# os_-_POC.net
KiCad netlist of a schematic drawn in EAGLE
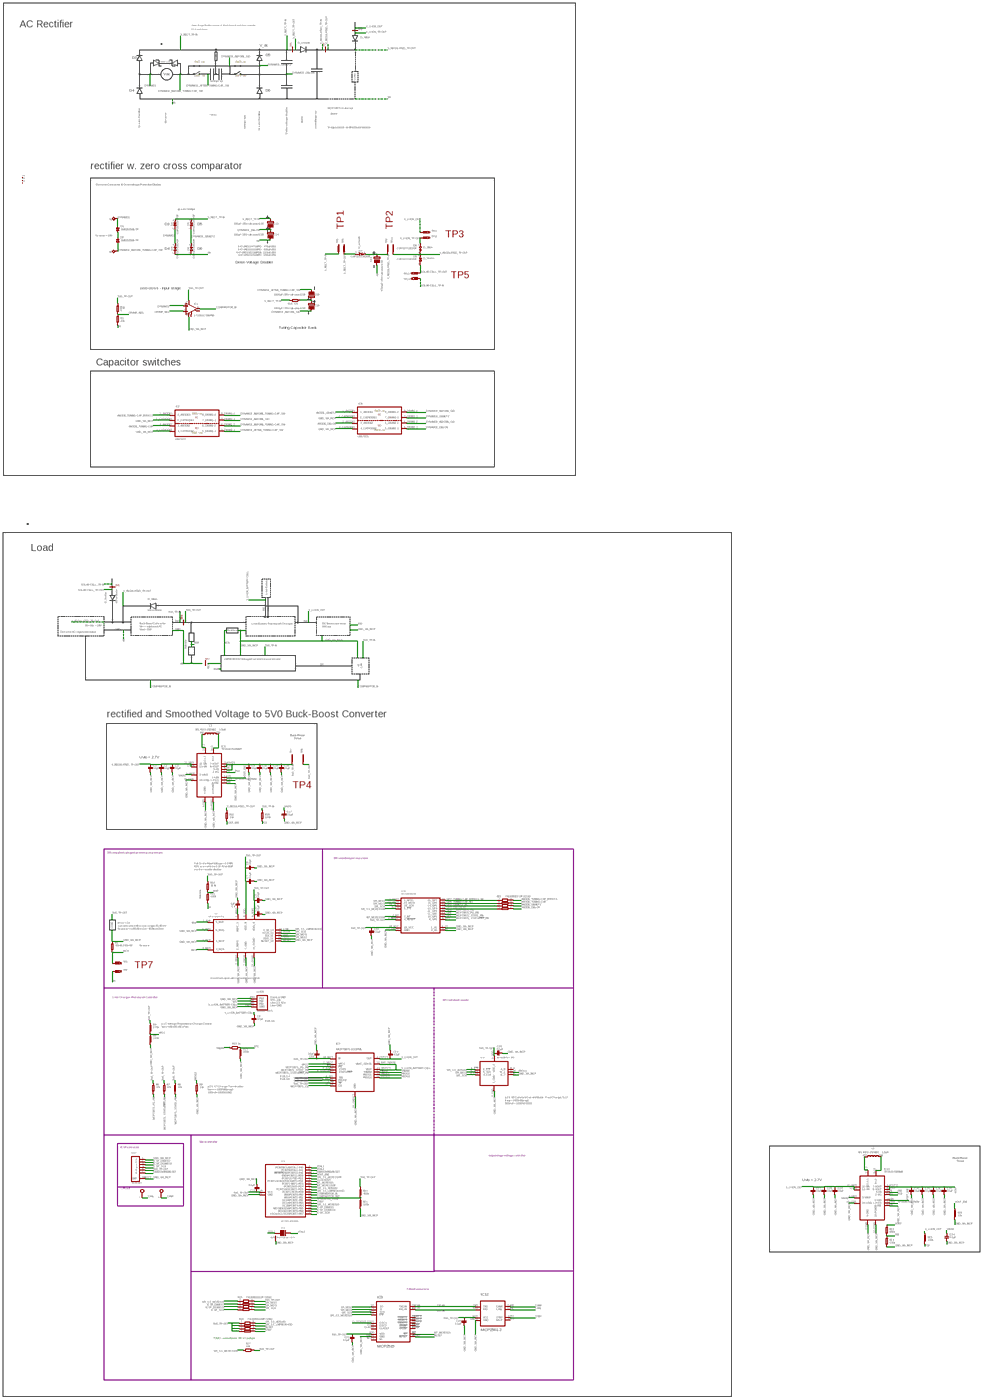
[diagram p0: schematic, sheet 1, overview]
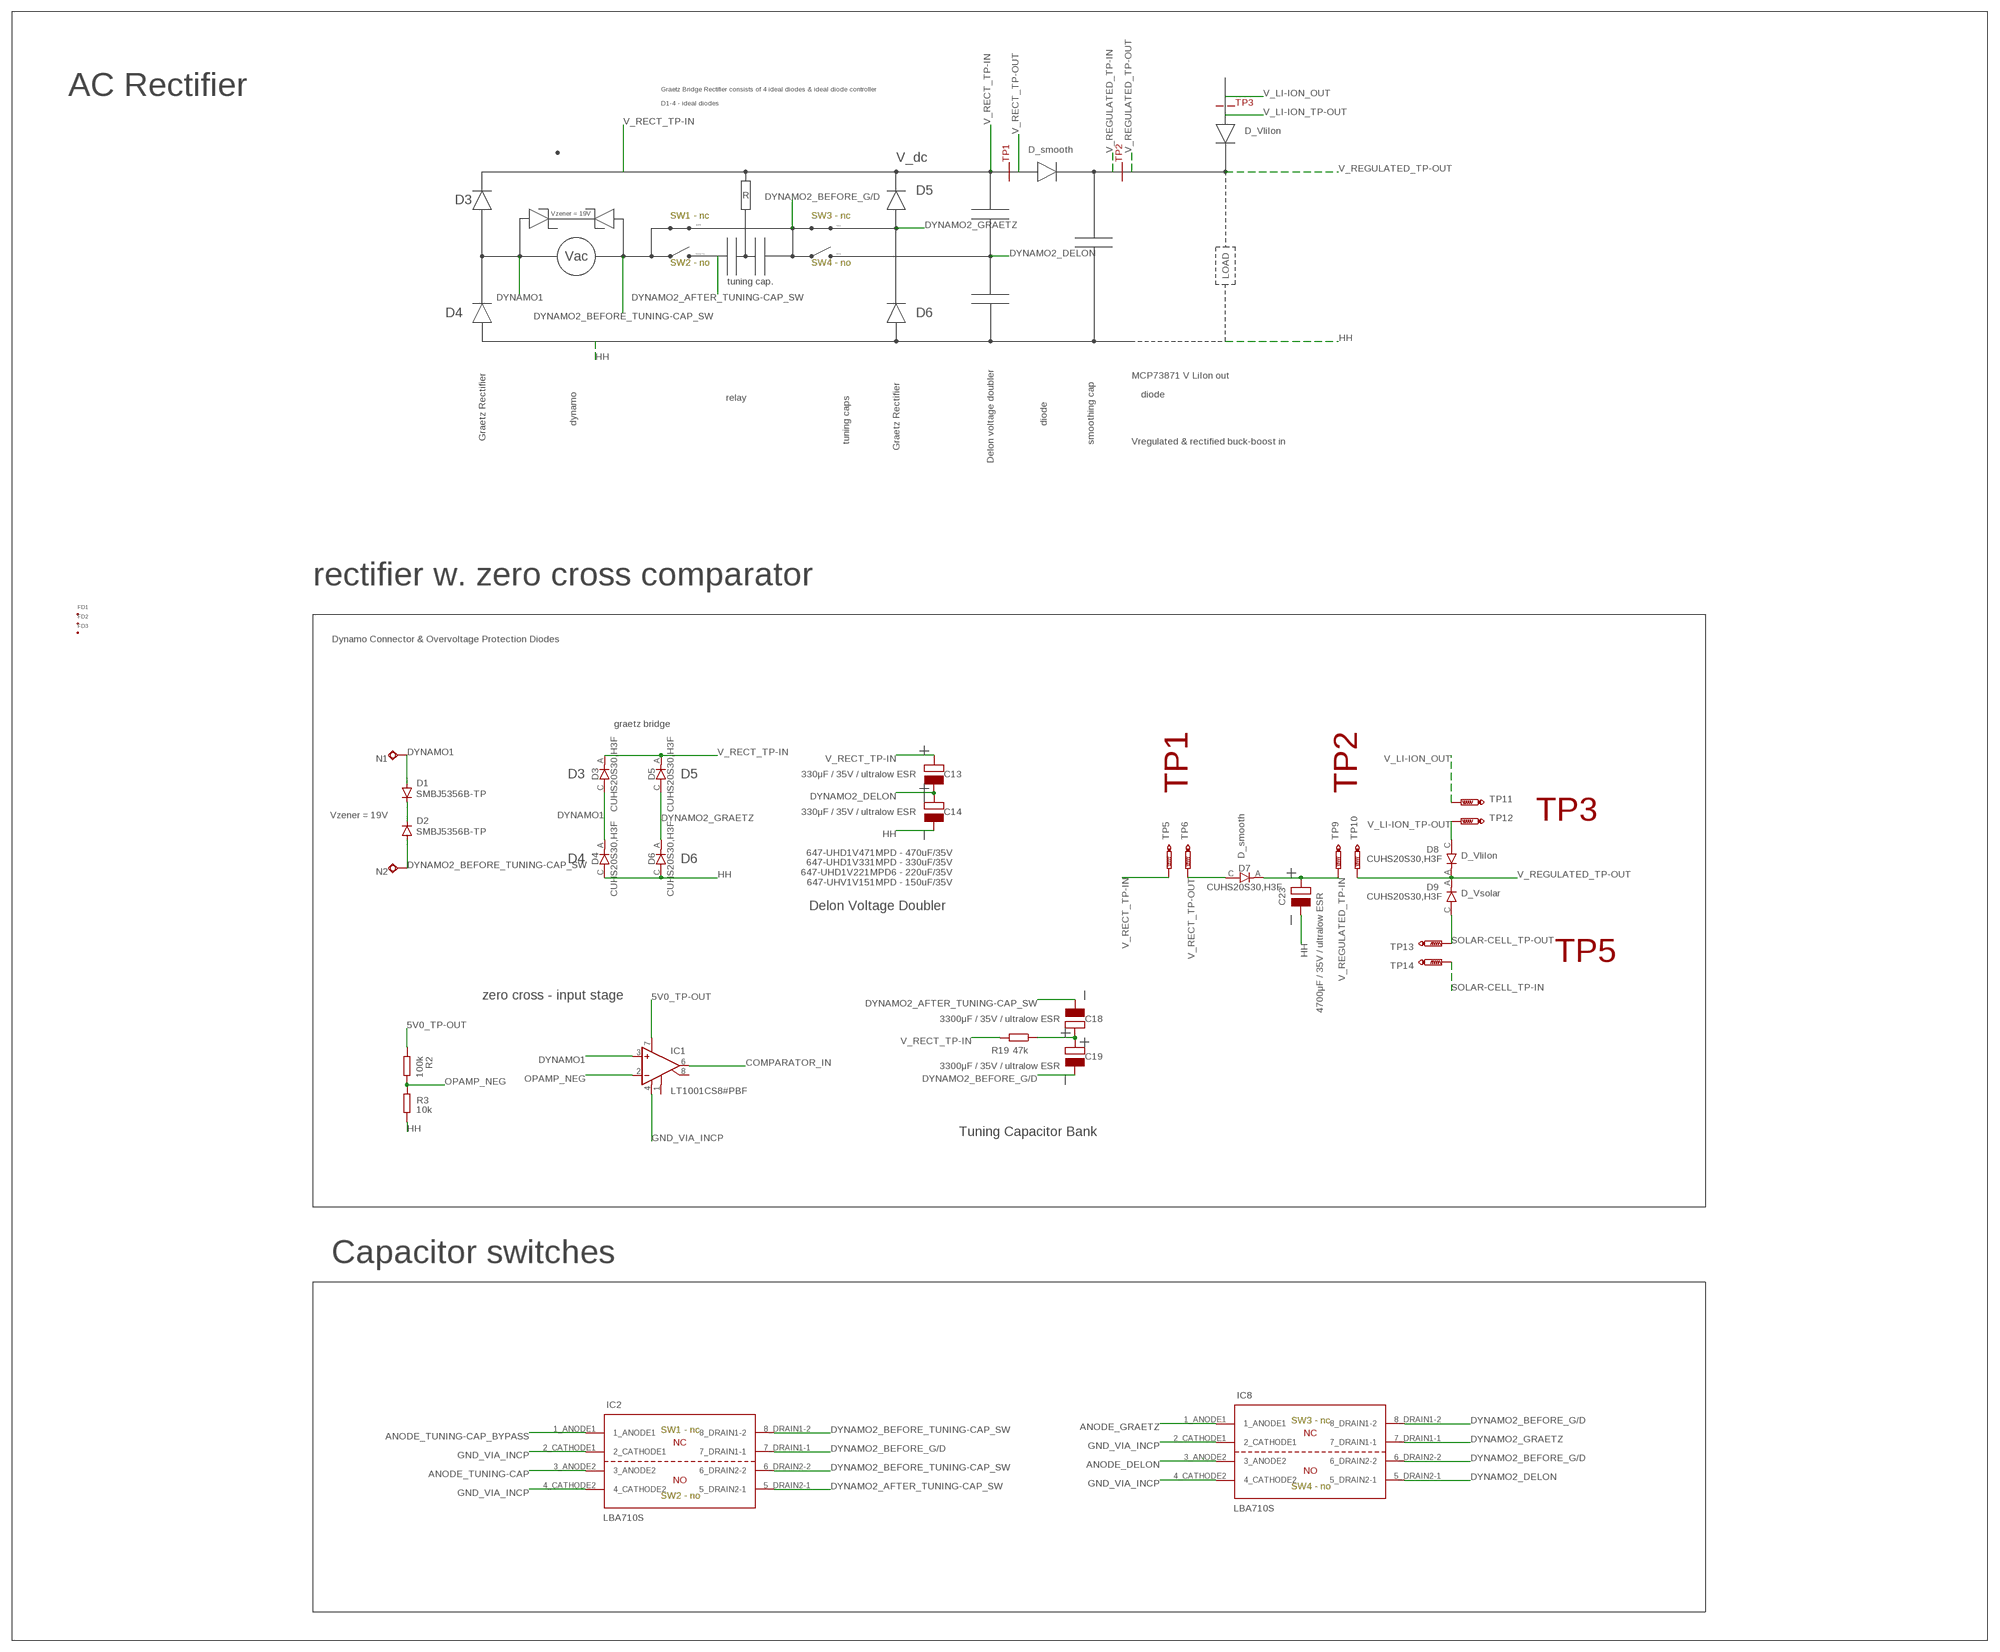
[diagram p1: schematic, sheet 1, part 1 of 5]
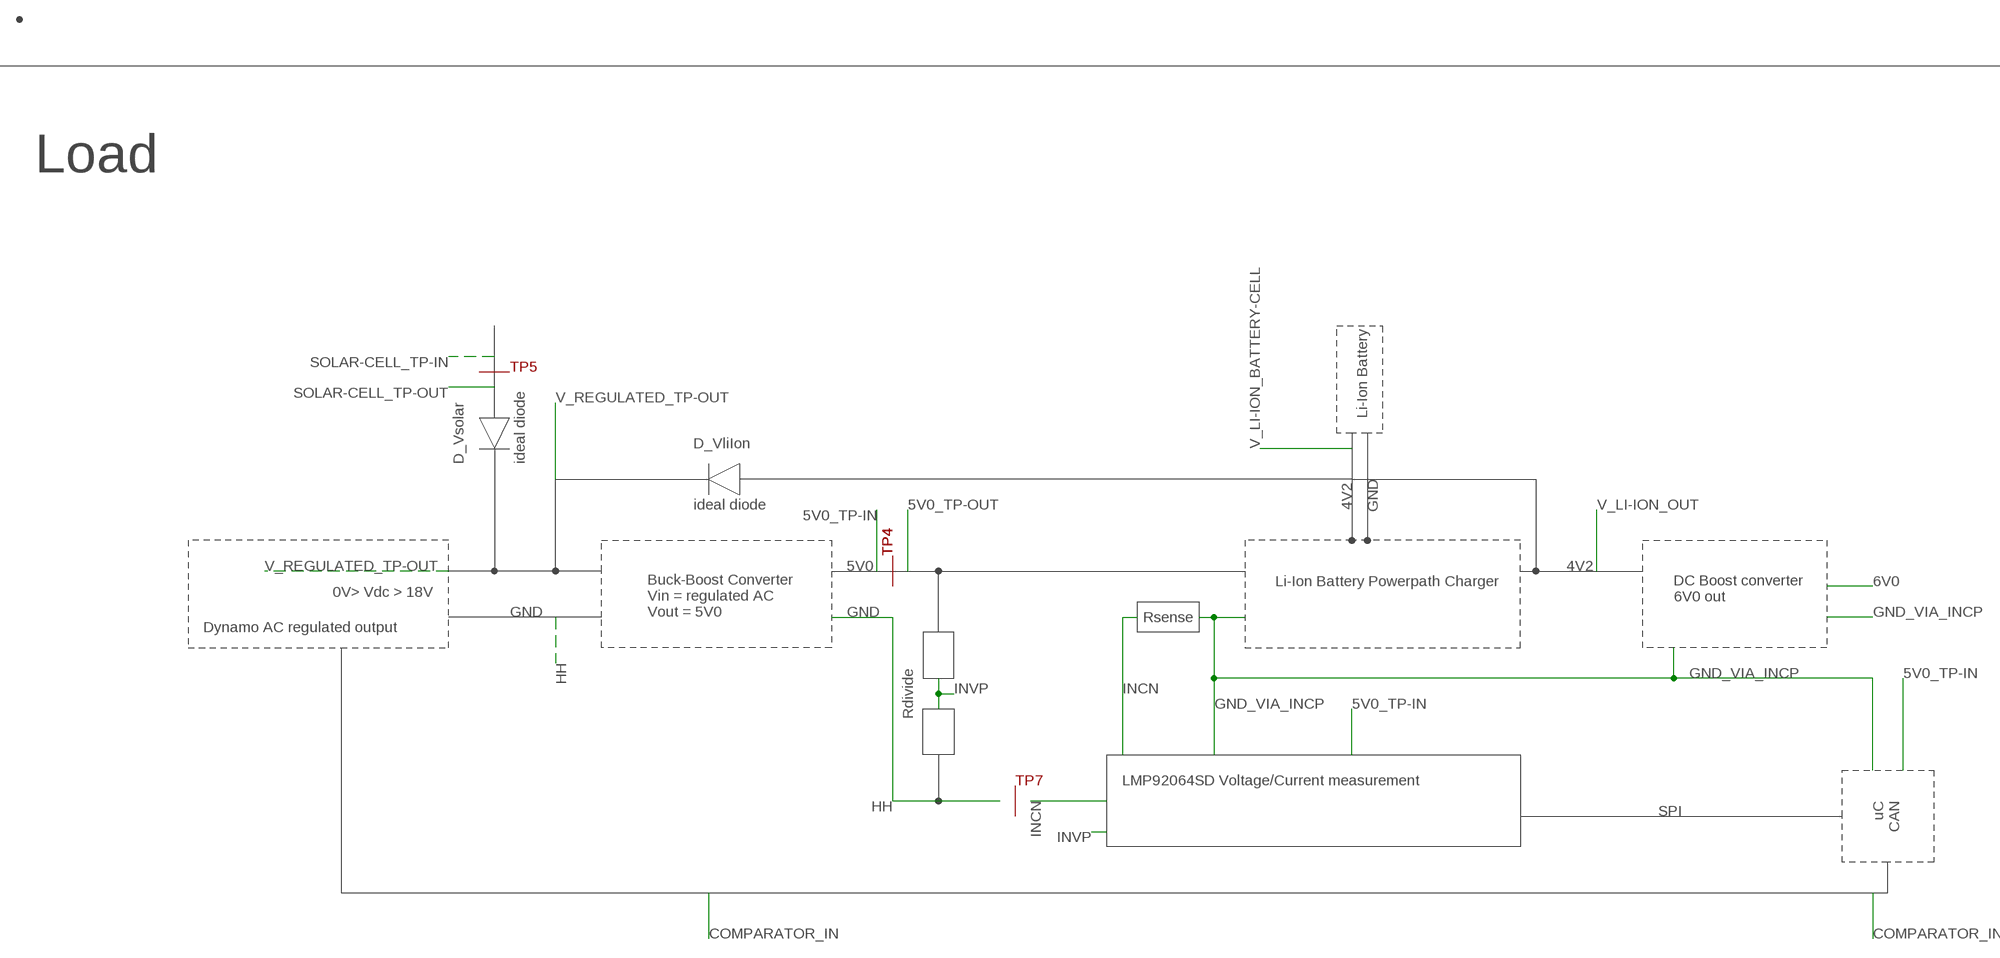
[diagram p2: schematic, sheet 1, part 2 of 5]
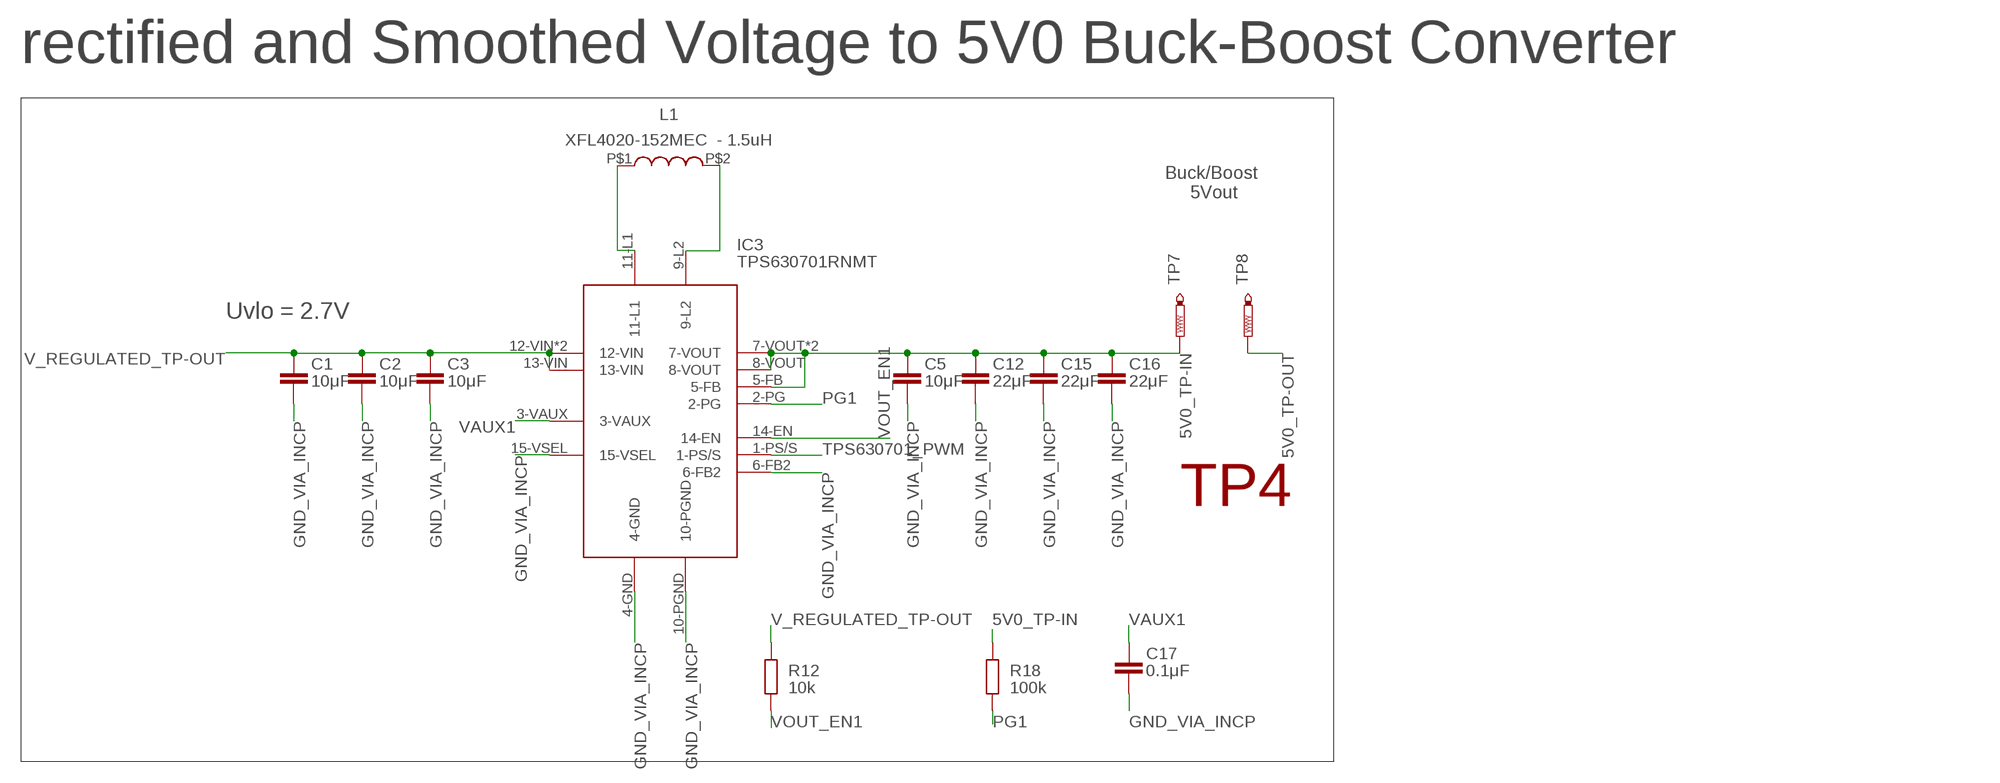
[diagram p3: schematic, sheet 1, part 3 of 5]
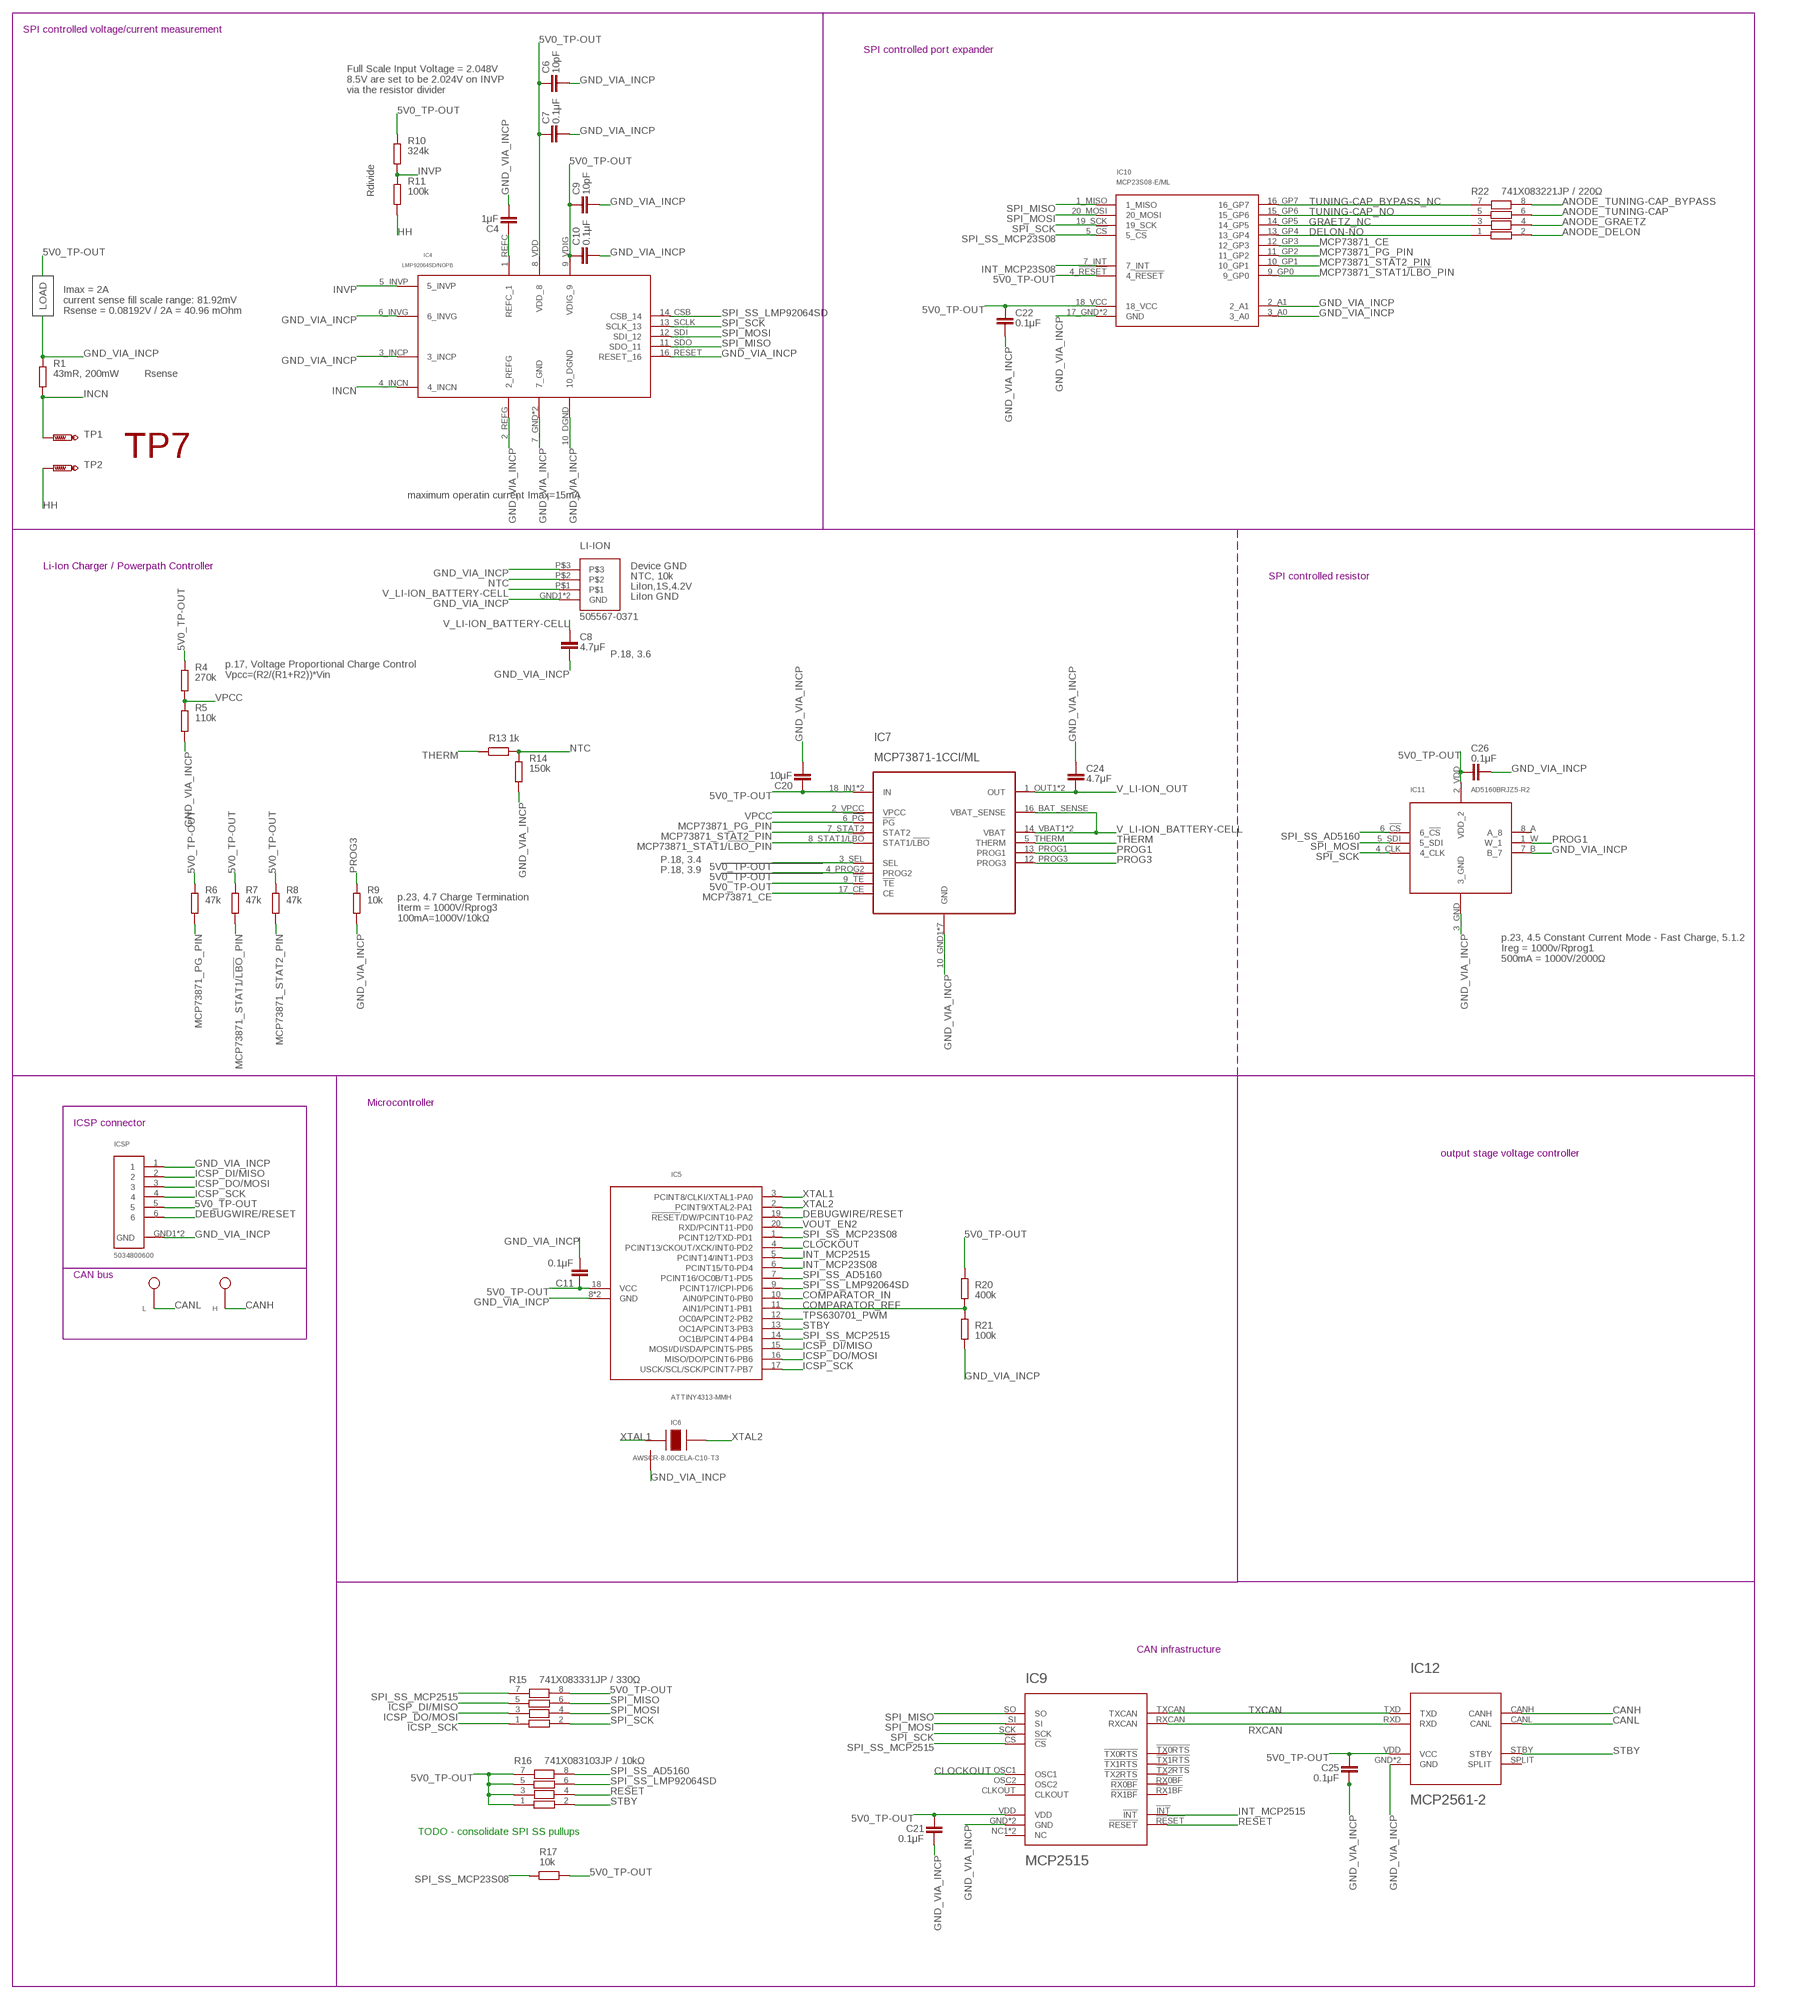
[diagram p4: schematic, sheet 1, part 4 of 5]
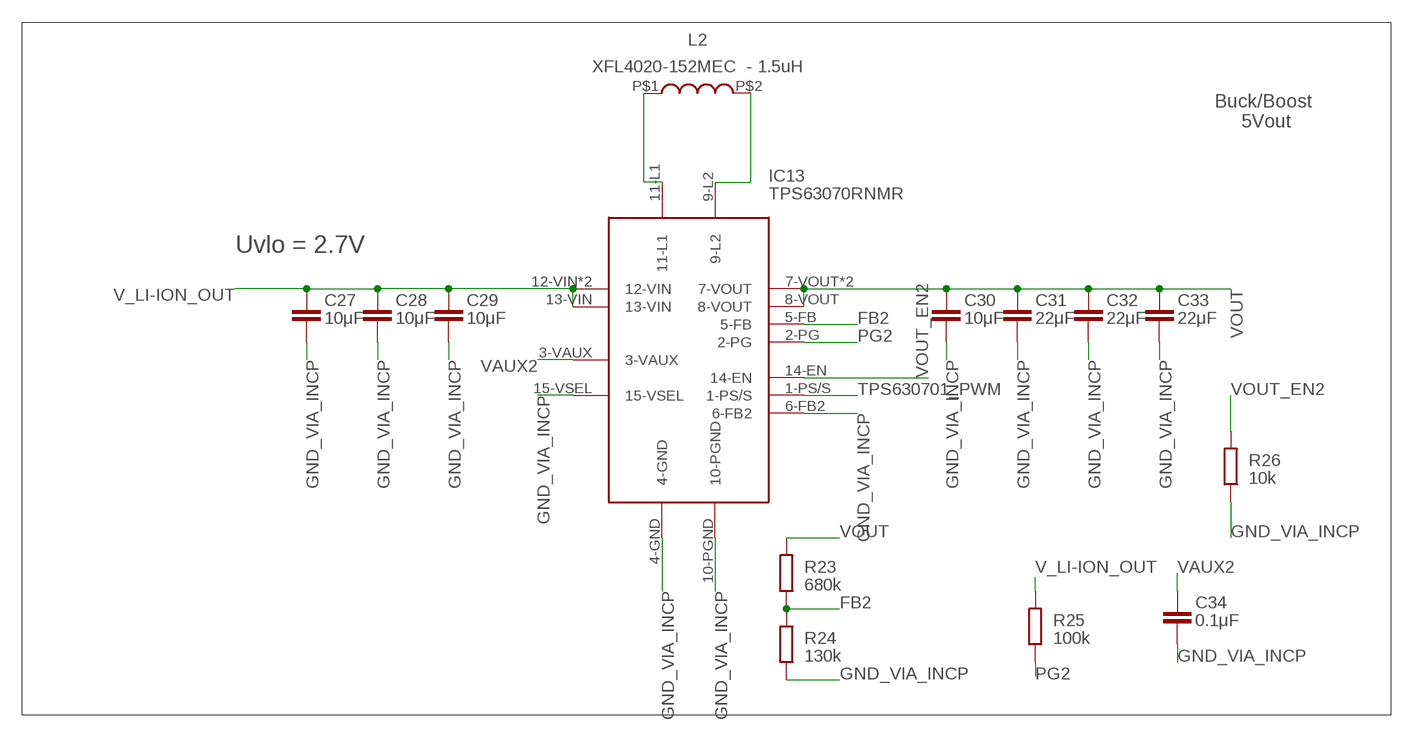
[diagram p5: schematic, sheet 1, part 5 of 5]

(export (version "E")
  (design (tool "Eeschema 10.0.6"))
  (components
    (comp (ref "C1")
      (value "10μF")
      (footprint "eagle-import:C0805")
      (libsource (lib "eagle-import") (part "C-EUC0805"))
    )
    (comp (ref "C2")
      (value "10μF")
      (footprint "eagle-import:C0805")
      (libsource (lib "eagle-import") (part "C-EUC0805"))
    )
    (comp (ref "C3")
      (value "10μF")
      (footprint "eagle-import:C0603")
      (libsource (lib "eagle-import") (part "C-EUC0603"))
    )
    (comp (ref "C4")
      (value "1μF")
      (footprint "eagle-import:C0402")
      (libsource (lib "eagle-import") (part "C-EUC0402"))
    )
    (comp (ref "C5")
      (value "10μF")
      (footprint "eagle-import:C0603")
      (libsource (lib "eagle-import") (part "C-EUC0603"))
    )
    (comp (ref "C6")
      (value "10pF")
      (footprint "eagle-import:C0402")
      (libsource (lib "eagle-import") (part "C-EUC0402"))
    )
    (comp (ref "C7")
      (value "0.1μF")
      (footprint "eagle-import:C0402")
      (libsource (lib "eagle-import") (part "C-EUC0402"))
    )
    (comp (ref "C8")
      (value "4.7μF")
      (footprint "eagle-import:C0402")
      (libsource (lib "eagle-import") (part "C-EUC0402"))
    )
    (comp (ref "C9")
      (value "10pF")
      (footprint "eagle-import:C0402")
      (libsource (lib "eagle-import") (part "C-EUC0402"))
    )
    (comp (ref "C10")
      (value "0.1μF")
      (footprint "eagle-import:C0402")
      (libsource (lib "eagle-import") (part "C-EUC0402"))
    )
    (comp (ref "C11")
      (value "0.1μF")
      (footprint "eagle-import:C0402")
      (libsource (lib "eagle-import") (part "C-EUC0402"))
    )
    (comp (ref "C12")
      (value "22μF")
      (footprint "eagle-import:C0805")
      (libsource (lib "eagle-import") (part "C-EUC0805"))
    )
    (comp (ref "C13")
      (value "330μF / 35V / ultralow ESR")
      (footprint "eagle-import:TH")
      (libsource (lib "eagle-import") (part "C-POL"))
    )
    (comp (ref "C14")
      (value "330μF / 35V / ultralow ESR")
      (footprint "eagle-import:TH")
      (libsource (lib "eagle-import") (part "C-POL"))
    )
    (comp (ref "C15")
      (value "22μF")
      (footprint "eagle-import:C0805")
      (libsource (lib "eagle-import") (part "C-EUC0805"))
    )
    (comp (ref "C16")
      (value "22μF")
      (footprint "eagle-import:C0805")
      (libsource (lib "eagle-import") (part "C-EUC0805"))
    )
    (comp (ref "C17")
      (value "0.1μF")
      (footprint "eagle-import:C0402")
      (libsource (lib "eagle-import") (part "C-EUC0402"))
    )
    (comp (ref "C18")
      (value "3300μF / 35V / ultralow ESR")
      (footprint "eagle-import:TH")
      (libsource (lib "eagle-import") (part "C-POL"))
    )
    (comp (ref "C19")
      (value "3300μF / 35V / ultralow ESR")
      (footprint "eagle-import:TH")
      (libsource (lib "eagle-import") (part "C-POL"))
    )
    (comp (ref "C20")
      (value "10μF")
      (footprint "eagle-import:C0402")
      (libsource (lib "eagle-import") (part "C-EUC0402"))
    )
    (comp (ref "C21")
      (value "0.1μF")
      (footprint "eagle-import:C0402")
      (libsource (lib "eagle-import") (part "C-EUC0402"))
    )
    (comp (ref "C22")
      (value "0.1μF")
      (footprint "eagle-import:C0402")
      (libsource (lib "eagle-import") (part "C-EUC0402"))
    )
    (comp (ref "C23")
      (value "4700μF / 35V / ultralow ESR")
      (footprint "eagle-import:TH")
      (libsource (lib "eagle-import") (part "C-POL"))
    )
    (comp (ref "C24")
      (value "4.7μF")
      (footprint "eagle-import:C0402")
      (libsource (lib "eagle-import") (part "C-EUC0402"))
    )
    (comp (ref "C25")
      (value "0.1μF")
      (footprint "eagle-import:C0402")
      (libsource (lib "eagle-import") (part "C-EUC0402"))
    )
    (comp (ref "C26")
      (value "0.1μF")
      (footprint "eagle-import:C0402")
      (libsource (lib "eagle-import") (part "C-EUC0402"))
    )
    (comp (ref "C27")
      (value "10μF")
      (footprint "eagle-import:C0805")
      (libsource (lib "eagle-import") (part "C-EUC0805"))
    )
    (comp (ref "C28")
      (value "10μF")
      (footprint "eagle-import:C0805")
      (libsource (lib "eagle-import") (part "C-EUC0805"))
    )
    (comp (ref "C29")
      (value "10μF")
      (footprint "eagle-import:C0603")
      (libsource (lib "eagle-import") (part "C-EUC0603"))
    )
    (comp (ref "C30")
      (value "10μF")
      (footprint "eagle-import:C0603")
      (libsource (lib "eagle-import") (part "C-EUC0603"))
    )
    (comp (ref "C31")
      (value "22μF")
      (footprint "eagle-import:C0805")
      (libsource (lib "eagle-import") (part "C-EUC0805"))
    )
    (comp (ref "C32")
      (value "22μF")
      (footprint "eagle-import:C0805")
      (libsource (lib "eagle-import") (part "C-EUC0805"))
    )
    (comp (ref "C33")
      (value "22μF")
      (footprint "eagle-import:C0805")
      (libsource (lib "eagle-import") (part "C-EUC0805"))
    )
    (comp (ref "C34")
      (value "0.1μF")
      (footprint "eagle-import:C0402")
      (libsource (lib "eagle-import") (part "C-EUC0402"))
    )
    (comp (ref "D1")
      (value "SMBJ5356B-TP")
      (footprint "eagle-import:DO214AA")
      (libsource (lib "eagle-import") (part "DIODE-DO214AA"))
    )
    (comp (ref "D2")
      (value "SMBJ5356B-TP")
      (footprint "eagle-import:DO214AA")
      (libsource (lib "eagle-import") (part "DIODE-DO214AA"))
    )
    (comp (ref "D3")
      (value "CUHS20S30,H3F")
      (footprint "eagle-import:US2H")
      (libsource (lib "eagle-import") (part "CUHS20S30"))
    )
    (comp (ref "D4")
      (value "CUHS20S30,H3F")
      (footprint "eagle-import:US2H")
      (libsource (lib "eagle-import") (part "CUHS20S30"))
    )
    (comp (ref "D5")
      (value "CUHS20S30,H3F")
      (footprint "eagle-import:US2H")
      (libsource (lib "eagle-import") (part "CUHS20S30"))
    )
    (comp (ref "D6")
      (value "CUHS20S30,H3F")
      (footprint "eagle-import:US2H")
      (libsource (lib "eagle-import") (part "CUHS20S30"))
    )
    (comp (ref "D7")
      (value "CUHS20S30,H3F")
      (footprint "eagle-import:US2H")
      (libsource (lib "eagle-import") (part "CUHS20S30"))
    )
    (comp (ref "D8")
      (value "CUHS20S30,H3F")
      (footprint "eagle-import:US2H")
      (libsource (lib "eagle-import") (part "CUHS20S30"))
    )
    (comp (ref "D9")
      (value "CUHS20S30,H3F")
      (footprint "eagle-import:US2H")
      (libsource (lib "eagle-import") (part "CUHS20S30"))
    )
    (comp (ref "FD1")
      (value "FID_40MIL")
      (footprint "eagle-import:FID_040")
      (libsource (lib "eagle-import") (part "FID_40MIL"))
    )
    (comp (ref "FD2")
      (value "FID_40MIL")
      (footprint "eagle-import:FID_040")
      (libsource (lib "eagle-import") (part "FID_40MIL"))
    )
    (comp (ref "FD3")
      (value "FID_40MIL")
      (footprint "eagle-import:FID_040")
      (libsource (lib "eagle-import") (part "FID_40MIL"))
    )
    (comp (ref "H")
      (value "CAN High")
      (footprint "eagle-import:SMT-1.2MM")
      (libsource (lib "eagle-import") (part "TPSMT-1.2MM"))
    )
    (comp (ref "IC1")
      (value "LT1001CS8#PBF")
      (footprint "eagle-import:SO08")
      (libsource (lib "eagle-import") (part "LT10S807C"))
    )
    (comp (ref "IC2")
      (value "LBA710S")
      (footprint "eagle-import:SMD_DIP6")
      (libsource (lib "eagle-import") (part "LBA710"))
    )
    (comp (ref "IC3")
      (value "TPS630701RNMT")
      (footprint "eagle-import:VQFN")
      (libsource (lib "eagle-import") (part "TPS630701"))
    )
    (comp (ref "IC4")
      (value "LMP92064SD/NOPB")
      (footprint "eagle-import:WSON-16")
      (libsource (lib "eagle-import") (part "LMP92064SD"))
    )
    (comp (ref "IC5")
      (value "ATTINY4313-MMH")
      (footprint "eagle-import:VQFN-20")
      (fields (field (name "SPICEPREFIX") "X"))
      (libsource (lib "eagle-import") (part "ATTINY4313VQFN-20"))
    )
    (comp (ref "IC6")
      (value "AWSCR-8.00CELA-C10-T3")
      (footprint "eagle-import:SMT")
      (libsource (lib "eagle-import") (part "PRQV"))
    )
    (comp (ref "IC7")
      (value "MCP73871-1CCI/ML")
      (footprint "eagle-import:QFN50P400X400X100-21N")
      (fields (field (name "MPN") "MCP73871-2AAI/ML"))
      (libsource (lib "eagle-import") (part "MCP73871-2AAI/ML"))
    )
    (comp (ref "IC8")
      (value "LBA710S")
      (footprint "eagle-import:SMD_DIP6")
      (libsource (lib "eagle-import") (part "LBA710"))
    )
    (comp (ref "IC9")
      (value "MCP2515")
      (footprint "eagle-import:QFN20")
      (libsource (lib "eagle-import") (part "MCP2515-I-ML"))
    )
    (comp (ref "IC10")
      (value "MCP23S08-E/ML")
      (footprint "eagle-import:QFN20")
      (libsource (lib "eagle-import") (part "MCP23S08"))
    )
    (comp (ref "IC11")
      (value "AD5160BRJZ5-R2")
      (footprint "eagle-import:SOT-23-8")
      (libsource (lib "eagle-import") (part "AD5160"))
    )
    (comp (ref "IC12")
      (value "MCP2561-2")
      (footprint "eagle-import:DFN10")
      (libsource (lib "eagle-import") (part "MCP2561-2"))
    )
    (comp (ref "IC13")
      (value "TPS63070RNMR")
      (footprint "eagle-import:VQFN")
      (libsource (lib "eagle-import") (part "TPS630701"))
    )
    (comp (ref "ICSP")
      (value "5034800600")
      (footprint "eagle-import:SMT")
      (libsource (lib "eagle-import") (part "5034800600"))
    )
    (comp (ref "L")
      (value "CAN Low")
      (footprint "eagle-import:SMT-1.2MM")
      (libsource (lib "eagle-import") (part "TPSMT-1.2MM"))
    )
    (comp (ref "L1")
      (value "XFL4020-152MEC - 1.5uH")
      (footprint "eagle-import:SMD")
      (libsource (lib "eagle-import") (part "XFL4020-152MEC"))
    )
    (comp (ref "L2")
      (value "XFL4020-152MEC - 1.5uH")
      (footprint "eagle-import:SMD")
      (libsource (lib "eagle-import") (part "XFL4020-152MEC"))
    )
    (comp (ref "LI-ION")
      (value "505567-0371")
      (footprint "eagle-import:SMT")
      (libsource (lib "eagle-import") (part "505567"))
    )
    (comp (ref "N1")
      (value "Li-Ion Cell +")
      (footprint "eagle-import:P1-13")
      (libsource (lib "eagle-import") (part "TPSQPAD1-13"))
    )
    (comp (ref "N2")
      (value "Li-Ion Cell +")
      (footprint "eagle-import:P1-13")
      (libsource (lib "eagle-import") (part "TPSQPAD1-13"))
    )
    (comp (ref "R1")
      (value "43mR, 200mW")
      (footprint "eagle-import:R2512")
      (libsource (lib "eagle-import") (part "R-EU_R2512"))
    )
    (comp (ref "R2")
      (value "100k")
      (footprint "eagle-import:R0402")
      (libsource (lib "eagle-import") (part "R-EU_R0402"))
    )
    (comp (ref "R3")
      (value "10k")
      (footprint "eagle-import:R0402")
      (libsource (lib "eagle-import") (part "R-EU_R0402"))
    )
    (comp (ref "R4")
      (value "270k")
      (footprint "eagle-import:R0402")
      (libsource (lib "eagle-import") (part "R-EU_R0402"))
    )
    (comp (ref "R5")
      (value "110k")
      (footprint "eagle-import:R0402")
      (libsource (lib "eagle-import") (part "R-EU_R0402"))
    )
    (comp (ref "R6")
      (value "47k")
      (footprint "eagle-import:R0402")
      (libsource (lib "eagle-import") (part "R-EU_R0402"))
    )
    (comp (ref "R7")
      (value "47k")
      (footprint "eagle-import:R0402")
      (libsource (lib "eagle-import") (part "R-EU_R0402"))
    )
    (comp (ref "R8")
      (value "47k")
      (footprint "eagle-import:R0402")
      (libsource (lib "eagle-import") (part "R-EU_R0402"))
    )
    (comp (ref "R9")
      (value "10k")
      (footprint "eagle-import:R0402")
      (libsource (lib "eagle-import") (part "R-EU_R0402"))
    )
    (comp (ref "R10")
      (value "324k")
      (footprint "eagle-import:R0402")
      (libsource (lib "eagle-import") (part "R-EU_R0402"))
    )
    (comp (ref "R11")
      (value "100k")
      (footprint "eagle-import:R0402")
      (libsource (lib "eagle-import") (part "R-EU_R0402"))
    )
    (comp (ref "R12")
      (value "10k")
      (footprint "eagle-import:R0402")
      (libsource (lib "eagle-import") (part "R-EU_R0402"))
    )
    (comp (ref "R13")
      (value "1k")
      (footprint "eagle-import:R0402")
      (libsource (lib "eagle-import") (part "R-EU_R0402"))
    )
    (comp (ref "R14")
      (value "150k")
      (footprint "eagle-import:R0402")
      (libsource (lib "eagle-import") (part "R-EU_R0402"))
    )
    (comp (ref "R15")
      (value "741X083331JP / 330Ω")
      (footprint "eagle-import:0402-4R")
      (libsource (lib "eagle-import") (part "741X083331JP"))
    )
    (comp (ref "R16")
      (value "741X083103JP / 10kΩ")
      (footprint "eagle-import:0402-4R")
      (libsource (lib "eagle-import") (part "741X083331JP"))
    )
    (comp (ref "R17")
      (value "10k")
      (footprint "eagle-import:R0402")
      (libsource (lib "eagle-import") (part "R-EU_R0402"))
    )
    (comp (ref "R18")
      (value "100k")
      (footprint "eagle-import:R0402")
      (libsource (lib "eagle-import") (part "R-EU_R0402"))
    )
    (comp (ref "R19")
      (value "47k")
      (footprint "eagle-import:R0402")
      (libsource (lib "eagle-import") (part "R-EU_R0402"))
    )
    (comp (ref "R20")
      (value "400k")
      (footprint "eagle-import:R0402")
      (libsource (lib "eagle-import") (part "R-EU_R0402"))
    )
    (comp (ref "R21")
      (value "100k")
      (footprint "eagle-import:R0402")
      (libsource (lib "eagle-import") (part "R-EU_R0402"))
    )
    (comp (ref "R22")
      (value "741X083221JP / 220Ω")
      (footprint "eagle-import:0402-4R")
      (libsource (lib "eagle-import") (part "741X083331JP"))
    )
    (comp (ref "R23")
      (value "680k")
      (footprint "eagle-import:R0402")
      (libsource (lib "eagle-import") (part "R-EU_R0402"))
    )
    (comp (ref "R24")
      (value "130k")
      (footprint "eagle-import:R0402")
      (libsource (lib "eagle-import") (part "R-EU_R0402"))
    )
    (comp (ref "R25")
      (value "100k")
      (footprint "eagle-import:R0402")
      (libsource (lib "eagle-import") (part "R-EU_R0402"))
    )
    (comp (ref "R26")
      (value "10k")
      (footprint "eagle-import:R0402")
      (libsource (lib "eagle-import") (part "R-EU_R0402"))
    )
    (comp (ref "TP1")
      (value "PTR1TP10SQ")
      (footprint "eagle-import:TP10SQ")
      (libsource (lib "eagle-import") (part "PTR1TP10SQ"))
    )
    (comp (ref "TP2")
      (value "PTR1TP10SQ")
      (footprint "eagle-import:TP10SQ")
      (libsource (lib "eagle-import") (part "PTR1TP10SQ"))
    )
    (comp (ref "TP5")
      (value "PTR1TP10SQ")
      (footprint "eagle-import:TP10SQ")
      (libsource (lib "eagle-import") (part "PTR1TP10SQ"))
    )
    (comp (ref "TP6")
      (value "PTR1TP10SQ")
      (footprint "eagle-import:TP10SQ")
      (libsource (lib "eagle-import") (part "PTR1TP10SQ"))
    )
    (comp (ref "TP7")
      (value "PTR1TP10SQ")
      (footprint "eagle-import:TP10SQ")
      (libsource (lib "eagle-import") (part "PTR1TP10SQ"))
    )
    (comp (ref "TP8")
      (value "PTR1TP10SQ")
      (footprint "eagle-import:TP10SQ")
      (libsource (lib "eagle-import") (part "PTR1TP10SQ"))
    )
    (comp (ref "TP9")
      (value "PTR1TP10SQ")
      (footprint "eagle-import:TP10SQ")
      (libsource (lib "eagle-import") (part "PTR1TP10SQ"))
    )
    (comp (ref "TP10")
      (value "PTR1TP10SQ")
      (footprint "eagle-import:TP10SQ")
      (libsource (lib "eagle-import") (part "PTR1TP10SQ"))
    )
    (comp (ref "TP11")
      (value "PTR1TP10SQ")
      (footprint "eagle-import:TP10SQ")
      (libsource (lib "eagle-import") (part "PTR1TP10SQ"))
    )
    (comp (ref "TP12")
      (value "PTR1TP10SQ")
      (footprint "eagle-import:TP10SQ")
      (libsource (lib "eagle-import") (part "PTR1TP10SQ"))
    )
    (comp (ref "TP13")
      (value "PTR1TP10SQ")
      (footprint "eagle-import:TP10SQ")
      (libsource (lib "eagle-import") (part "PTR1TP10SQ"))
    )
    (comp (ref "TP14")
      (value "PTR1TP10SQ")
      (footprint "eagle-import:TP10SQ")
      (libsource (lib "eagle-import") (part "PTR1TP10SQ"))
    )
  )
  (nets
    (net (code "1") (name "/5V0_TP-IN") (class "Default")
      (node (ref "C12") (pin "1") (pinfunction "1_1") (pintype "passive"))
      (node (ref "C15") (pin "1") (pinfunction "1_1") (pintype "passive"))
      (node (ref "C16") (pin "1") (pinfunction "1_1") (pintype "passive"))
      (node (ref "C5") (pin "1") (pinfunction "1_1") (pintype "passive"))
      (node (ref "IC3") (pin "5-FB") (pinfunction "5-FB_5-FB") (pintype "bidirectional"))
      (node (ref "IC3") (pin "7-VOUT") (pinfunction "7-VOUT_7-VOUT") (pintype "bidirectional"))
      (node (ref "IC3") (pin "8-VOUT") (pinfunction "8-VOUT_8-VOUT") (pintype "bidirectional"))
      (node (ref "IC3") (pin "VOUT") (pinfunction "7-VOUT_VOUT") (pintype "bidirectional"))
      (node (ref "R18") (pin "2") (pinfunction "2_2") (pintype "passive"))
      (node (ref "TP7") (pin "TP") (pinfunction "TP_TP") (pintype "input"))
    )
    (net (code "2") (name "/5V0_TP-OUT") (class "Default")
      (node (ref "C10") (pin "1") (pinfunction "1_1") (pintype "passive"))
      (node (ref "C11") (pin "1") (pinfunction "1_1") (pintype "passive"))
      (node (ref "C20") (pin "1") (pinfunction "1_1") (pintype "passive"))
      (node (ref "C21") (pin "1") (pinfunction "1_1") (pintype "passive"))
      (node (ref "C22") (pin "1") (pinfunction "1_1") (pintype "passive"))
      (node (ref "C25") (pin "1") (pinfunction "1_1") (pintype "passive"))
      (node (ref "C26") (pin "1") (pinfunction "1_1") (pintype "passive"))
      (node (ref "C6") (pin "1") (pinfunction "1_1") (pintype "passive"))
      (node (ref "C7") (pin "1") (pinfunction "1_1") (pintype "passive"))
      (node (ref "C9") (pin "1") (pinfunction "1_1") (pintype "passive"))
      (node (ref "IC1") (pin "7") (pinfunction "V+_7") (pintype "power_in"))
      (node (ref "IC10") (pin "18_VCC") (pinfunction "18_VCC_18_VCC") (pintype "power_in"))
      (node (ref "IC10") (pin "4_!RESET!") (pinfunction "4_~{RESET}_4_!RESET!") (pintype "input"))
      (node (ref "IC11") (pin "2_VDD") (pinfunction "VDD_2_2_VDD") (pintype "bidirectional"))
      (node (ref "IC12") (pin "VDD") (pinfunction "VCC_VDD") (pintype "power_in"))
      (node (ref "IC4") (pin "8_VDD") (pinfunction "VDD_8_8_VDD") (pintype "power_in"))
      (node (ref "IC4") (pin "9_VDIG") (pinfunction "VDIG_9_9_VDIG") (pintype "power_in"))
      (node (ref "IC5") (pin "18") (pinfunction "VCC_18") (pintype "bidirectional"))
      (node (ref "IC7") (pin "18_IN1") (pinfunction "IN_18_IN1") (pintype "power_in"))
      (node (ref "IC7") (pin "19_IN2") (pinfunction "IN_19_IN2") (pintype "power_in"))
      (node (ref "IC7") (pin "3_SEL") (pinfunction "SEL_3_SEL") (pintype "input"))
      (node (ref "IC7") (pin "4_PROG2") (pinfunction "PROG2_4_PROG2") (pintype "input"))
      (node (ref "IC7") (pin "9_!TE!") (pinfunction "~{TE}_9_!TE!") (pintype "input"))
      (node (ref "IC9") (pin "VDD") (pinfunction "VDD_VDD") (pintype "power_in"))
      (node (ref "ICSP") (pin "5") (pinfunction "5_5") (pintype "bidirectional"))
      (node (ref "R10") (pin "2") (pinfunction "2_2") (pintype "passive"))
      (node (ref "R15") (pin "8") (pinfunction "8_8") (pintype "bidirectional"))
      (node (ref "R16") (pin "1") (pinfunction "1_1") (pintype "bidirectional"))
      (node (ref "R16") (pin "3") (pinfunction "3_3") (pintype "bidirectional"))
      (node (ref "R16") (pin "5") (pinfunction "5_5") (pintype "bidirectional"))
      (node (ref "R16") (pin "7") (pinfunction "7_7") (pintype "bidirectional"))
      (node (ref "R17") (pin "2") (pinfunction "2_2") (pintype "passive"))
      (node (ref "R2") (pin "1") (pinfunction "1_1") (pintype "passive"))
      (node (ref "R20") (pin "1") (pinfunction "1_1") (pintype "passive"))
      (node (ref "R4") (pin "2") (pinfunction "2_2") (pintype "passive"))
      (node (ref "R6") (pin "2") (pinfunction "2_2") (pintype "passive"))
      (node (ref "R7") (pin "2") (pinfunction "2_2") (pintype "passive"))
      (node (ref "R8") (pin "2") (pinfunction "2_2") (pintype "passive"))
      (node (ref "TP8") (pin "TP") (pinfunction "TP_TP") (pintype "input"))
    )
    (net (code "4") (name "/ANODE_DELON") (class "Default")
      (node (ref "IC8") (pin "3_ANODE2") (pinfunction "3_ANODE2_3_ANODE2") (pintype "input"))
      (node (ref "R22") (pin "2") (pinfunction "2_2") (pintype "bidirectional"))
    )
    (net (code "5") (name "/ANODE_GRAETZ") (class "Default")
      (node (ref "IC8") (pin "1_ANODE1") (pinfunction "1_ANODE1_1_ANODE1") (pintype "input"))
      (node (ref "R22") (pin "4") (pinfunction "4_4") (pintype "bidirectional"))
    )
    (net (code "6") (name "/ANODE_TUNING-CAP") (class "Default")
      (node (ref "IC2") (pin "3_ANODE2") (pinfunction "3_ANODE2_3_ANODE2") (pintype "input"))
      (node (ref "R22") (pin "6") (pinfunction "6_6") (pintype "bidirectional"))
    )
    (net (code "7") (name "/ANODE_TUNING-CAP_BYPASS") (class "Default")
      (node (ref "IC2") (pin "1_ANODE1") (pinfunction "1_ANODE1_1_ANODE1") (pintype "input"))
      (node (ref "R22") (pin "8") (pinfunction "8_8") (pintype "bidirectional"))
    )
    (net (code "8") (name "/CANH") (class "Default")
      (node (ref "H") (pin "P$1") (pinfunction "TP$1_P$1") (pintype "bidirectional"))
      (node (ref "IC12") (pin "CANH") (pinfunction "CANH_CANH") (pintype "bidirectional"))
    )
    (net (code "9") (name "/CANL") (class "Default")
      (node (ref "IC12") (pin "CANL") (pinfunction "CANL_CANL") (pintype "bidirectional"))
      (node (ref "L") (pin "P$1") (pinfunction "TP$1_P$1") (pintype "bidirectional"))
    )
    (net (code "10") (name "/CLOCKOUT") (class "Default")
      (node (ref "IC5") (pin "4") (pinfunction "PCINT13/CKOUT/XCK/INT0-PD2_4") (pintype "bidirectional"))
      (node (ref "IC9") (pin "OSC1") (pinfunction "OSC1_OSC1") (pintype "bidirectional"))
    )
    (net (code "11") (name "/COMPARATOR_IN") (class "Default")
      (node (ref "IC1") (pin "6") (pinfunction "OUT_6") (pintype "output"))
      (node (ref "IC5") (pin "10") (pinfunction "AIN0/PCINT0-PB0_10") (pintype "bidirectional"))
    )
    (net (code "12") (name "/COMPARATOR_REF") (class "Default")
      (node (ref "IC5") (pin "11") (pinfunction "AIN1/PCINT1-PB1_11") (pintype "bidirectional"))
      (node (ref "R20") (pin "2") (pinfunction "2_2") (pintype "passive"))
      (node (ref "R21") (pin "1") (pinfunction "1_1") (pintype "passive"))
    )
    (net (code "13") (name "/DEBUGWIRE{slash}RESET") (class "Default")
      (node (ref "IC5") (pin "19") (pinfunction "~{RESET}/DW/PCINT10-PA2_19") (pintype "bidirectional"))
      (node (ref "ICSP") (pin "6") (pinfunction "6_6") (pintype "bidirectional"))
    )
    (net (code "14") (name "/DELON-NO") (class "Default")
      (node (ref "IC10") (pin "13_GP4") (pinfunction "13_GP4_13_GP4") (pintype "bidirectional"))
      (node (ref "R22") (pin "1") (pinfunction "1_1") (pintype "bidirectional"))
    )
    (net (code "15") (name "/DYNAMO1") (class "Default")
      (node (ref "D1") (pin "A") (pinfunction "A_A") (pintype "passive"))
      (node (ref "D3") (pin "C") (pinfunction "C_C") (pintype "bidirectional"))
      (node (ref "D4") (pin "A") (pinfunction "A_A") (pintype "bidirectional"))
      (node (ref "IC1") (pin "3") (pinfunction "+IN_3") (pintype "input"))
      (node (ref "N1") (pin "TP") (pinfunction "TP_TP") (pintype "input"))
    )
    (net (code "16") (name "/DYNAMO2_AFTER_TUNING-CAP_SW") (class "Default")
      (node (ref "C18") (pin "NEG") (pinfunction "NEG_NEG") (pintype "bidirectional"))
      (node (ref "IC2") (pin "5_DRAIN2-1") (pinfunction "5_DRAIN2-1_5_DRAIN2-1") (pintype "bidirectional"))
    )
    (net (code "17") (name "/DYNAMO2_BEFORE_G{slash}D") (class "Default")
      (node (ref "C19") (pin "NEG") (pinfunction "NEG_NEG") (pintype "bidirectional"))
      (node (ref "IC2") (pin "7_DRAIN1-1") (pinfunction "7_DRAIN1-1_7_DRAIN1-1") (pintype "bidirectional"))
      (node (ref "IC8") (pin "6_DRAIN2-2") (pinfunction "6_DRAIN2-2_6_DRAIN2-2") (pintype "bidirectional"))
      (node (ref "IC8") (pin "8_DRAIN1-2") (pinfunction "8_DRAIN1-2_8_DRAIN1-2") (pintype "bidirectional"))
    )
    (net (code "18") (name "/DYNAMO2_BEFORE_TUNING-CAP_SW") (class "Default")
      (node (ref "D2") (pin "A") (pinfunction "A_A") (pintype "passive"))
      (node (ref "IC2") (pin "6_DRAIN2-2") (pinfunction "6_DRAIN2-2_6_DRAIN2-2") (pintype "bidirectional"))
      (node (ref "IC2") (pin "8_DRAIN1-2") (pinfunction "8_DRAIN1-2_8_DRAIN1-2") (pintype "bidirectional"))
      (node (ref "N2") (pin "TP") (pinfunction "TP_TP") (pintype "input"))
    )
    (net (code "19") (name "/DYNAMO2_DELON") (class "Default")
      (node (ref "C13") (pin "NEG") (pinfunction "NEG_NEG") (pintype "bidirectional"))
      (node (ref "C14") (pin "POS") (pinfunction "POS_POS") (pintype "bidirectional"))
      (node (ref "IC8") (pin "5_DRAIN2-1") (pinfunction "5_DRAIN2-1_5_DRAIN2-1") (pintype "bidirectional"))
    )
    (net (code "20") (name "/DYNAMO2_GRAETZ") (class "Default")
      (node (ref "D5") (pin "C") (pinfunction "C_C") (pintype "bidirectional"))
      (node (ref "D6") (pin "A") (pinfunction "A_A") (pintype "bidirectional"))
      (node (ref "IC8") (pin "7_DRAIN1-1") (pinfunction "7_DRAIN1-1_7_DRAIN1-1") (pintype "bidirectional"))
    )
    (net (code "21") (name "/FB2") (class "Default")
      (node (ref "IC13") (pin "5-FB") (pinfunction "5-FB_5-FB") (pintype "bidirectional"))
      (node (ref "R23") (pin "1") (pinfunction "1_1") (pintype "passive"))
      (node (ref "R24") (pin "2") (pinfunction "2_2") (pintype "passive"))
    )
    (net (code "22") (name "/GND_VIA_INCP") (class "Default")
      (node (ref "C1") (pin "2") (pinfunction "2_2") (pintype "passive"))
      (node (ref "C10") (pin "2") (pinfunction "2_2") (pintype "passive"))
      (node (ref "C11") (pin "2") (pinfunction "2_2") (pintype "passive"))
      (node (ref "C12") (pin "2") (pinfunction "2_2") (pintype "passive"))
      (node (ref "C15") (pin "2") (pinfunction "2_2") (pintype "passive"))
      (node (ref "C16") (pin "2") (pinfunction "2_2") (pintype "passive"))
      (node (ref "C17") (pin "2") (pinfunction "2_2") (pintype "passive"))
      (node (ref "C2") (pin "2") (pinfunction "2_2") (pintype "passive"))
      (node (ref "C20") (pin "2") (pinfunction "2_2") (pintype "passive"))
      (node (ref "C21") (pin "2") (pinfunction "2_2") (pintype "passive"))
      (node (ref "C22") (pin "2") (pinfunction "2_2") (pintype "passive"))
      (node (ref "C24") (pin "1") (pinfunction "1_1") (pintype "passive"))
      (node (ref "C25") (pin "2") (pinfunction "2_2") (pintype "passive"))
      (node (ref "C26") (pin "2") (pinfunction "2_2") (pintype "passive"))
      (node (ref "C27") (pin "2") (pinfunction "2_2") (pintype "passive"))
      (node (ref "C28") (pin "2") (pinfunction "2_2") (pintype "passive"))
      (node (ref "C29") (pin "2") (pinfunction "2_2") (pintype "passive"))
      (node (ref "C3") (pin "2") (pinfunction "2_2") (pintype "passive"))
      (node (ref "C30") (pin "2") (pinfunction "2_2") (pintype "passive"))
      (node (ref "C31") (pin "2") (pinfunction "2_2") (pintype "passive"))
      (node (ref "C32") (pin "2") (pinfunction "2_2") (pintype "passive"))
      (node (ref "C33") (pin "2") (pinfunction "2_2") (pintype "passive"))
      (node (ref "C34") (pin "2") (pinfunction "2_2") (pintype "passive"))
      (node (ref "C4") (pin "2") (pinfunction "2_2") (pintype "passive"))
      (node (ref "C5") (pin "2") (pinfunction "2_2") (pintype "passive"))
      (node (ref "C6") (pin "2") (pinfunction "2_2") (pintype "passive"))
      (node (ref "C7") (pin "2") (pinfunction "2_2") (pintype "passive"))
      (node (ref "C8") (pin "2") (pinfunction "2_2") (pintype "passive"))
      (node (ref "C9") (pin "2") (pinfunction "2_2") (pintype "passive"))
      (node (ref "IC1") (pin "4") (pinfunction "V-_4") (pintype "power_in"))
      (node (ref "IC10") (pin "17_GND") (pinfunction "GND_17_GND") (pintype "power_in"))
      (node (ref "IC10") (pin "2_A1") (pinfunction "2_A1_2_A1") (pintype "input"))
      (node (ref "IC10") (pin "3_A0") (pinfunction "3_A0_3_A0") (pintype "input"))
      (node (ref "IC10") (pin "GND") (pinfunction "GND_GND") (pintype "power_in"))
      (node (ref "IC11") (pin "3_GND") (pinfunction "3_GND_3_GND") (pintype "bidirectional"))
      (node (ref "IC11") (pin "7_B") (pinfunction "B_7_7_B") (pintype "bidirectional"))
      (node (ref "IC12") (pin "GND") (pinfunction "GND_GND") (pintype "power_in"))
      (node (ref "IC12") (pin "VSS") (pinfunction "GND_VSS") (pintype "power_in"))
      (node (ref "IC13") (pin "10-PGND") (pinfunction "10-PGND_10-PGND") (pintype "bidirectional"))
      (node (ref "IC13") (pin "15-VSEL") (pinfunction "15-VSEL_15-VSEL") (pintype "bidirectional"))
      (node (ref "IC13") (pin "4-GND") (pinfunction "4-GND_4-GND") (pintype "bidirectional"))
      (node (ref "IC13") (pin "6-FB2") (pinfunction "6-FB2_6-FB2") (pintype "bidirectional"))
      (node (ref "IC2") (pin "2_CATHODE1") (pinfunction "2_CATHODE1_2_CATHODE1") (pintype "output"))
      (node (ref "IC2") (pin "4_CATHODE2") (pinfunction "4_CATHODE2_4_CATHODE2") (pintype "output"))
      (node (ref "IC3") (pin "10-PGND") (pinfunction "10-PGND_10-PGND") (pintype "bidirectional"))
      (node (ref "IC3") (pin "15-VSEL") (pinfunction "15-VSEL_15-VSEL") (pintype "bidirectional"))
      (node (ref "IC3") (pin "4-GND") (pinfunction "4-GND_4-GND") (pintype "bidirectional"))
      (node (ref "IC3") (pin "6-FB2") (pinfunction "6-FB2_6-FB2") (pintype "bidirectional"))
      (node (ref "IC4") (pin "10_DGND") (pinfunction "10_DGND_10_DGND") (pintype "power_in"))
      (node (ref "IC4") (pin "16_RESET") (pinfunction "RESET_16_16_RESET") (pintype "input"))
      (node (ref "IC4") (pin "2_REFG") (pinfunction "2_REFG_2_REFG") (pintype "power_in"))
      (node (ref "IC4") (pin "3_INCP") (pinfunction "3_INCP_3_INCP") (pintype "input"))
      (node (ref "IC4") (pin "6_INVG") (pinfunction "6_INVG_6_INVG") (pintype "output"))
      (node (ref "IC4") (pin "7_GND") (pinfunction "7_GND_7_GND") (pintype "power_in"))
      (node (ref "IC4") (pin "GND1") (pinfunction "7_GND_GND1") (pintype "power_in"))
      (node (ref "IC5") (pin "8") (pinfunction "GND_8") (pintype "bidirectional"))
      (node (ref "IC5") (pin "GND") (pinfunction "GND_GND") (pintype "bidirectional"))
      (node (ref "IC6") (pin "GND") (pinfunction "GND_GND") (pintype "bidirectional"))
      (node (ref "IC7") (pin "10_GND1") (pinfunction "GND_10_GND1") (pintype "bidirectional"))
      (node (ref "IC7") (pin "11_GND2") (pinfunction "GND_11_GND2") (pintype "bidirectional"))
      (node (ref "IC7") (pin "GND2") (pinfunction "GND_GND2") (pintype "bidirectional"))
      (node (ref "IC7") (pin "GND3") (pinfunction "GND_GND3") (pintype "bidirectional"))
      (node (ref "IC7") (pin "GND4") (pinfunction "GND_GND4") (pintype "bidirectional"))
      (node (ref "IC7") (pin "GND5") (pinfunction "GND_GND5") (pintype "bidirectional"))
      (node (ref "IC7") (pin "GND6") (pinfunction "GND_GND6") (pintype "bidirectional"))
      (node (ref "IC8") (pin "2_CATHODE1") (pinfunction "2_CATHODE1_2_CATHODE1") (pintype "output"))
      (node (ref "IC8") (pin "4_CATHODE2") (pinfunction "4_CATHODE2_4_CATHODE2") (pintype "output"))
      (node (ref "IC9") (pin "GND") (pinfunction "GND_GND") (pintype "power_in"))
      (node (ref "IC9") (pin "GND6") (pinfunction "GND_GND6") (pintype "power_in"))
      (node (ref "ICSP") (pin "1") (pinfunction "1_1") (pintype "bidirectional"))
      (node (ref "ICSP") (pin "GND1") (pinfunction "GND_GND1") (pintype "bidirectional"))
      (node (ref "ICSP") (pin "GND2") (pinfunction "GND_GND2") (pintype "bidirectional"))
      (node (ref "LI-ION") (pin "GND1") (pinfunction "GND_GND1") (pintype "bidirectional"))
      (node (ref "LI-ION") (pin "GND2") (pinfunction "GND_GND2") (pintype "bidirectional"))
      (node (ref "LI-ION") (pin "P$3") (pinfunction "P$3_P$3") (pintype "bidirectional"))
      (node (ref "R1") (pin "2") (pinfunction "2_2") (pintype "passive"))
      (node (ref "R14") (pin "1") (pinfunction "1_1") (pintype "passive"))
      (node (ref "R21") (pin "2") (pinfunction "2_2") (pintype "passive"))
      (node (ref "R24") (pin "1") (pinfunction "1_1") (pintype "passive"))
      (node (ref "R26") (pin "1") (pinfunction "1_1") (pintype "passive"))
      (node (ref "R5") (pin "1") (pinfunction "1_1") (pintype "passive"))
      (node (ref "R9") (pin "1") (pinfunction "1_1") (pintype "passive"))
    )
    (net (code "23") (name "/GRAETZ_NC") (class "Default")
      (node (ref "IC10") (pin "14_GP5") (pinfunction "14_GP5_14_GP5") (pintype "bidirectional"))
      (node (ref "R22") (pin "3") (pinfunction "3_3") (pintype "bidirectional"))
    )
    (net (code "24") (name "/HH") (class "Default")
      (node (ref "C14") (pin "NEG") (pinfunction "NEG_NEG") (pintype "bidirectional"))
      (node (ref "C23") (pin "NEG") (pinfunction "NEG_NEG") (pintype "bidirectional"))
      (node (ref "D4") (pin "C") (pinfunction "C_C") (pintype "bidirectional"))
      (node (ref "D6") (pin "C") (pinfunction "C_C") (pintype "bidirectional"))
      (node (ref "R11") (pin "1") (pinfunction "1_1") (pintype "passive"))
      (node (ref "R3") (pin "1") (pinfunction "1_1") (pintype "passive"))
      (node (ref "TP2") (pin "TP") (pinfunction "TP_TP") (pintype "input"))
    )
    (net (code "25") (name "/ICSP_DI{slash}MISO") (class "Default")
      (node (ref "IC5") (pin "15") (pinfunction "MOSI/DI/SDA/PCINT5-PB5_15") (pintype "bidirectional"))
      (node (ref "ICSP") (pin "2") (pinfunction "2_2") (pintype "bidirectional"))
      (node (ref "R15") (pin "5") (pinfunction "5_5") (pintype "bidirectional"))
    )
    (net (code "26") (name "/ICSP_DO{slash}MOSI") (class "Default")
      (node (ref "IC5") (pin "16") (pinfunction "MISO/DO/PCINT6-PB6_16") (pintype "bidirectional"))
      (node (ref "ICSP") (pin "3") (pinfunction "3_3") (pintype "bidirectional"))
      (node (ref "R15") (pin "3") (pinfunction "3_3") (pintype "bidirectional"))
    )
    (net (code "27") (name "/ICSP_SCK") (class "Default")
      (node (ref "IC5") (pin "17") (pinfunction "USCK/SCL/SCK/PCINT7-PB7_17") (pintype "bidirectional"))
      (node (ref "ICSP") (pin "4") (pinfunction "4_4") (pintype "bidirectional"))
      (node (ref "R15") (pin "1") (pinfunction "1_1") (pintype "bidirectional"))
    )
    (net (code "28") (name "/INCN") (class "Default")
      (node (ref "IC4") (pin "4_INCN") (pinfunction "4_INCN_4_INCN") (pintype "output"))
      (node (ref "R1") (pin "1") (pinfunction "1_1") (pintype "passive"))
      (node (ref "TP1") (pin "TP") (pinfunction "TP_TP") (pintype "input"))
    )
    (net (code "29") (name "/INT_MCP23S08") (class "Default")
      (node (ref "IC10") (pin "7_INT") (pinfunction "7_INT_7_INT") (pintype "output"))
      (node (ref "IC5") (pin "6") (pinfunction "PCINT15/T0-PD4_6") (pintype "bidirectional"))
    )
    (net (code "30") (name "/INT_MCP2515") (class "Default")
      (node (ref "IC5") (pin "5") (pinfunction "PCINT14/INT1-PD3_5") (pintype "bidirectional"))
      (node (ref "IC9") (pin "!INT!") (pinfunction "~{INT}_!INT!") (pintype "bidirectional"))
    )
    (net (code "31") (name "/INVP") (class "Default")
      (node (ref "IC4") (pin "5_INVP") (pinfunction "5_INVP_5_INVP") (pintype "input"))
      (node (ref "R10") (pin "1") (pinfunction "1_1") (pintype "passive"))
      (node (ref "R11") (pin "2") (pinfunction "2_2") (pintype "passive"))
    )
    (net (code "32") (name "/MCP73871_CE") (class "Default")
      (node (ref "IC10") (pin "12_GP3") (pinfunction "12_GP3_12_GP3") (pintype "bidirectional"))
      (node (ref "IC7") (pin "17_CE") (pinfunction "CE_17_CE") (pintype "input"))
    )
    (net (code "33") (name "/MCP73871_PG_PIN") (class "Default")
      (node (ref "IC10") (pin "11_GP2") (pinfunction "11_GP2_11_GP2") (pintype "bidirectional"))
      (node (ref "IC7") (pin "!6_PG!") (pinfunction "~{PG}_!6_PG!") (pintype "output"))
      (node (ref "R6") (pin "1") (pinfunction "1_1") (pintype "passive"))
    )
    (net (code "34") (name "/MCP73871_STAT1{slash}~{LBO}_PIN") (class "Default")
      (node (ref "IC10") (pin "9_GP0") (pinfunction "9_GP0_9_GP0") (pintype "bidirectional"))
      (node (ref "IC7") (pin "8_STAT1/!LBO!") (pinfunction "STAT1/~{LBO}_8_STAT1/!LBO!") (pintype "output"))
      (node (ref "R7") (pin "1") (pinfunction "1_1") (pintype "passive"))
    )
    (net (code "35") (name "/MCP73871_STAT2_PIN") (class "Default")
      (node (ref "IC10") (pin "10_GP1") (pinfunction "10_GP1_10_GP1") (pintype "bidirectional"))
      (node (ref "IC7") (pin "7_STAT2") (pinfunction "STAT2_7_STAT2") (pintype "output"))
      (node (ref "R8") (pin "1") (pinfunction "1_1") (pintype "passive"))
    )
    (net (code "36") (name "/NTC") (class "Default")
      (node (ref "LI-ION") (pin "P$2") (pinfunction "P$2_P$2") (pintype "bidirectional"))
      (node (ref "R13") (pin "2") (pinfunction "2_2") (pintype "passive"))
      (node (ref "R14") (pin "2") (pinfunction "2_2") (pintype "passive"))
    )
    (net (code "37") (name "/OPAMP_NEG") (class "Default")
      (node (ref "IC1") (pin "2") (pinfunction "-IN_2") (pintype "input"))
      (node (ref "R2") (pin "2") (pinfunction "2_2") (pintype "passive"))
      (node (ref "R3") (pin "2") (pinfunction "2_2") (pintype "passive"))
    )
    (net (code "38") (name "/PG1") (class "Default")
      (node (ref "IC3") (pin "2-PG") (pinfunction "2-PG_2-PG") (pintype "bidirectional"))
      (node (ref "R18") (pin "1") (pinfunction "1_1") (pintype "passive"))
    )
    (net (code "39") (name "/PG2") (class "Default")
      (node (ref "IC13") (pin "2-PG") (pinfunction "2-PG_2-PG") (pintype "bidirectional"))
      (node (ref "R25") (pin "1") (pinfunction "1_1") (pintype "passive"))
    )
    (net (code "40") (name "/PROG1") (class "Default")
      (node (ref "IC11") (pin "1_W") (pinfunction "W_1_1_W") (pintype "bidirectional"))
      (node (ref "IC7") (pin "13_PROG1") (pinfunction "PROG1_13_PROG1") (pintype "bidirectional"))
    )
    (net (code "41") (name "/PROG3") (class "Default")
      (node (ref "IC7") (pin "12_PROG3") (pinfunction "PROG3_12_PROG3") (pintype "bidirectional"))
      (node (ref "R9") (pin "2") (pinfunction "2_2") (pintype "passive"))
    )
    (net (code "42") (name "/RESET") (class "Default")
      (node (ref "IC9") (pin "!RESET!") (pinfunction "~{RESET}_!RESET!") (pintype "bidirectional"))
      (node (ref "R16") (pin "4") (pinfunction "4_4") (pintype "bidirectional"))
    )
    (net (code "43") (name "/RXCAN") (class "Default")
      (node (ref "IC12") (pin "RXD") (pinfunction "RXD_RXD") (pintype "output"))
      (node (ref "IC9") (pin "RXCAN") (pinfunction "RXCAN_RXCAN") (pintype "input"))
    )
    (net (code "44") (name "/SOLAR-CELL_TP-IN") (class "Default")
      (node (ref "TP14") (pin "TP") (pinfunction "TP_TP") (pintype "input"))
    )
    (net (code "45") (name "/SOLAR-CELL_TP-OUT") (class "Default")
      (node (ref "D9") (pin "C") (pinfunction "C_C") (pintype "bidirectional"))
      (node (ref "TP13") (pin "TP") (pinfunction "TP_TP") (pintype "input"))
    )
    (net (code "46") (name "/SPI_MISO") (class "Default")
      (node (ref "IC10") (pin "1_MISO") (pinfunction "1_MISO_1_MISO") (pintype "output"))
      (node (ref "IC4") (pin "11_SDO") (pinfunction "SDO_11_11_SDO") (pintype "output"))
      (node (ref "IC9") (pin "SO") (pinfunction "SO_SO") (pintype "output"))
      (node (ref "R15") (pin "6") (pinfunction "6_6") (pintype "bidirectional"))
    )
    (net (code "47") (name "/SPI_MOSI") (class "Default")
      (node (ref "IC10") (pin "20_MOSI") (pinfunction "20_MOSI_20_MOSI") (pintype "input"))
      (node (ref "IC11") (pin "5_SDI") (pinfunction "5_SDI_5_SDI") (pintype "bidirectional"))
      (node (ref "IC4") (pin "12_SDI") (pinfunction "SDI_12_12_SDI") (pintype "input"))
      (node (ref "IC9") (pin "SI") (pinfunction "SI_SI") (pintype "input"))
      (node (ref "R15") (pin "4") (pinfunction "4_4") (pintype "bidirectional"))
    )
    (net (code "48") (name "/SPI_SCK") (class "Default")
      (node (ref "IC10") (pin "19_SCK") (pinfunction "19_SCK_19_SCK") (pintype "input"))
      (node (ref "IC11") (pin "4_CLK") (pinfunction "4_CLK_4_CLK") (pintype "bidirectional"))
      (node (ref "IC4") (pin "13_SCLK") (pinfunction "SCLK_13_13_SCLK") (pintype "input"))
      (node (ref "IC9") (pin "SCK") (pinfunction "SCK_SCK") (pintype "bidirectional"))
      (node (ref "R15") (pin "2") (pinfunction "2_2") (pintype "bidirectional"))
    )
    (net (code "49") (name "/SPI_SS_AD5160") (class "Default")
      (node (ref "IC11") (pin "6_!CS!") (pinfunction "6_~{CS}_6_!CS!") (pintype "bidirectional"))
      (node (ref "IC5") (pin "7") (pinfunction "PCINT16/OC0B/T1-PD5_7") (pintype "bidirectional"))
      (node (ref "R16") (pin "8") (pinfunction "8_8") (pintype "bidirectional"))
    )
    (net (code "50") (name "/SPI_SS_LMP92064SD") (class "Default")
      (node (ref "IC4") (pin "14_CSB") (pinfunction "CSB_14_14_CSB") (pintype "bidirectional"))
      (node (ref "IC5") (pin "9") (pinfunction "PCINT17/ICPI-PD6_9") (pintype "bidirectional"))
      (node (ref "R16") (pin "6") (pinfunction "6_6") (pintype "bidirectional"))
    )
    (net (code "51") (name "/SPI_SS_MCP23S08") (class "Default")
      (node (ref "IC10") (pin "5_!CS!") (pinfunction "5_~{CS}_5_!CS!") (pintype "input"))
      (node (ref "IC5") (pin "1") (pinfunction "PCINT12/TXD-PD1_1") (pintype "bidirectional"))
      (node (ref "R17") (pin "1") (pinfunction "1_1") (pintype "passive"))
    )
    (net (code "52") (name "/SPI_SS_MCP2515") (class "Default")
      (node (ref "IC5") (pin "14") (pinfunction "OC1B/PCINT4-PB4_14") (pintype "bidirectional"))
      (node (ref "IC9") (pin "!CS!") (pinfunction "~{CS}_!CS!") (pintype "bidirectional"))
      (node (ref "R15") (pin "7") (pinfunction "7_7") (pintype "bidirectional"))
    )
    (net (code "53") (name "/STBY") (class "Default")
      (node (ref "IC12") (pin "STBY") (pinfunction "STBY_STBY") (pintype "bidirectional"))
      (node (ref "IC5") (pin "13") (pinfunction "OC1A/PCINT3-PB3_13") (pintype "bidirectional"))
      (node (ref "R16") (pin "2") (pinfunction "2_2") (pintype "bidirectional"))
    )
    (net (code "54") (name "/THERM") (class "Default")
      (node (ref "IC7") (pin "5_THERM") (pinfunction "THERM_5_THERM") (pintype "bidirectional"))
      (node (ref "R13") (pin "1") (pinfunction "1_1") (pintype "passive"))
    )
    (net (code "55") (name "/TPS630701_PWM") (class "Default")
      (node (ref "IC13") (pin "1-PS/S") (pinfunction "1-PS/S_1-PS/S") (pintype "bidirectional"))
      (node (ref "IC3") (pin "1-PS/S") (pinfunction "1-PS/S_1-PS/S") (pintype "bidirectional"))
      (node (ref "IC5") (pin "12") (pinfunction "OC0A/PCINT2-PB2_12") (pintype "bidirectional"))
    )
    (net (code "56") (name "/TUNING-CAP_BYPASS_NC") (class "Default")
      (node (ref "IC10") (pin "16_GP7") (pinfunction "16_GP7_16_GP7") (pintype "bidirectional"))
      (node (ref "R22") (pin "7") (pinfunction "7_7") (pintype "bidirectional"))
    )
    (net (code "57") (name "/TUNING-CAP_NO") (class "Default")
      (node (ref "IC10") (pin "15_GP6") (pinfunction "15_GP6_15_GP6") (pintype "bidirectional"))
      (node (ref "R22") (pin "5") (pinfunction "5_5") (pintype "bidirectional"))
    )
    (net (code "58") (name "/TXCAN") (class "Default")
      (node (ref "IC12") (pin "TXD") (pinfunction "TXD_TXD") (pintype "input"))
      (node (ref "IC9") (pin "TXCAN") (pinfunction "TXCAN_TXCAN") (pintype "output"))
    )
    (net (code "59") (name "/VAUX1") (class "Default")
      (node (ref "C17") (pin "1") (pinfunction "1_1") (pintype "passive"))
      (node (ref "IC3") (pin "3-VAUX") (pinfunction "3-VAUX_3-VAUX") (pintype "bidirectional"))
    )
    (net (code "60") (name "/VAUX2") (class "Default")
      (node (ref "C34") (pin "1") (pinfunction "1_1") (pintype "passive"))
      (node (ref "IC13") (pin "3-VAUX") (pinfunction "3-VAUX_3-VAUX") (pintype "bidirectional"))
    )
    (net (code "61") (name "/VOUT") (class "Default")
      (node (ref "C30") (pin "1") (pinfunction "1_1") (pintype "passive"))
      (node (ref "C31") (pin "1") (pinfunction "1_1") (pintype "passive"))
      (node (ref "C32") (pin "1") (pinfunction "1_1") (pintype "passive"))
      (node (ref "C33") (pin "1") (pinfunction "1_1") (pintype "passive"))
      (node (ref "IC13") (pin "7-VOUT") (pinfunction "7-VOUT_7-VOUT") (pintype "bidirectional"))
      (node (ref "IC13") (pin "8-VOUT") (pinfunction "8-VOUT_8-VOUT") (pintype "bidirectional"))
      (node (ref "IC13") (pin "VOUT") (pinfunction "7-VOUT_VOUT") (pintype "bidirectional"))
      (node (ref "R23") (pin "2") (pinfunction "2_2") (pintype "passive"))
    )
    (net (code "62") (name "/VOUT_EN1") (class "Default")
      (node (ref "IC3") (pin "14-EN") (pinfunction "14-EN_14-EN") (pintype "bidirectional"))
      (node (ref "R12") (pin "1") (pinfunction "1_1") (pintype "passive"))
    )
    (net (code "63") (name "/VOUT_EN2") (class "Default")
      (node (ref "IC13") (pin "14-EN") (pinfunction "14-EN_14-EN") (pintype "bidirectional"))
      (node (ref "IC5") (pin "20") (pinfunction "RXD/PCINT11-PD0_20") (pintype "bidirectional"))
      (node (ref "R26") (pin "2") (pinfunction "2_2") (pintype "passive"))
    )
    (net (code "64") (name "/VPCC") (class "Default")
      (node (ref "IC7") (pin "2_VPCC") (pinfunction "VPCC_2_VPCC") (pintype "input"))
      (node (ref "R4") (pin "1") (pinfunction "1_1") (pintype "passive"))
      (node (ref "R5") (pin "2") (pinfunction "2_2") (pintype "passive"))
    )
    (net (code "65") (name "/V_LI-ION_BATTERY-CELL") (class "Default")
      (node (ref "C8") (pin "1") (pinfunction "1_1") (pintype "passive"))
      (node (ref "IC7") (pin "14_VBAT1") (pinfunction "VBAT_14_VBAT1") (pintype "power_in"))
      (node (ref "IC7") (pin "15_VBAT2") (pinfunction "VBAT_15_VBAT2") (pintype "power_in"))
      (node (ref "IC7") (pin "16_BAT_SENSE") (pinfunction "VBAT_SENSE_16_BAT_SENSE") (pintype "bidirectional"))
      (node (ref "LI-ION") (pin "P$1") (pinfunction "P$1_P$1") (pintype "bidirectional"))
    )
    (net (code "66") (name "/V_LI-ION_OUT") (class "Default")
      (node (ref "C24") (pin "2") (pinfunction "2_2") (pintype "passive"))
      (node (ref "C27") (pin "1") (pinfunction "1_1") (pintype "passive"))
      (node (ref "C28") (pin "1") (pinfunction "1_1") (pintype "passive"))
      (node (ref "C29") (pin "1") (pinfunction "1_1") (pintype "passive"))
      (node (ref "IC13") (pin "12-VIN") (pinfunction "12-VIN_12-VIN") (pintype "bidirectional"))
      (node (ref "IC13") (pin "13-VIN") (pinfunction "13-VIN_13-VIN") (pintype "bidirectional"))
      (node (ref "IC13") (pin "VIN") (pinfunction "12-VIN_VIN") (pintype "bidirectional"))
      (node (ref "IC7") (pin "1_OUT1") (pinfunction "OUT_1_OUT1") (pintype "power_in"))
      (node (ref "IC7") (pin "20_OUT2") (pinfunction "OUT_20_OUT2") (pintype "power_in"))
      (node (ref "R25") (pin "2") (pinfunction "2_2") (pintype "passive"))
      (node (ref "TP11") (pin "TP") (pinfunction "TP_TP") (pintype "input"))
    )
    (net (code "67") (name "/V_LI-ION_TP-OUT") (class "Default")
      (node (ref "D8") (pin "C") (pinfunction "C_C") (pintype "bidirectional"))
      (node (ref "TP12") (pin "TP") (pinfunction "TP_TP") (pintype "input"))
    )
    (net (code "68") (name "/V_RECT_TP-IN") (class "Default")
      (node (ref "C13") (pin "POS") (pinfunction "POS_POS") (pintype "bidirectional"))
      (node (ref "D3") (pin "A") (pinfunction "A_A") (pintype "bidirectional"))
      (node (ref "D5") (pin "A") (pinfunction "A_A") (pintype "bidirectional"))
      (node (ref "R19") (pin "2") (pinfunction "2_2") (pintype "passive"))
      (node (ref "TP5") (pin "TP") (pinfunction "TP_TP") (pintype "input"))
    )
    (net (code "69") (name "/V_RECT_TP-OUT") (class "Default")
      (node (ref "D7") (pin "C") (pinfunction "C_C") (pintype "bidirectional"))
      (node (ref "TP6") (pin "TP") (pinfunction "TP_TP") (pintype "input"))
    )
    (net (code "70") (name "/V_REGULATED_TP-IN") (class "Default")
      (node (ref "C23") (pin "POS") (pinfunction "POS_POS") (pintype "bidirectional"))
      (node (ref "D7") (pin "A") (pinfunction "A_A") (pintype "bidirectional"))
      (node (ref "TP9") (pin "TP") (pinfunction "TP_TP") (pintype "input"))
    )
    (net (code "71") (name "/V_REGULATED_TP-OUT") (class "Default")
      (node (ref "C1") (pin "1") (pinfunction "1_1") (pintype "passive"))
      (node (ref "C2") (pin "1") (pinfunction "1_1") (pintype "passive"))
      (node (ref "C3") (pin "1") (pinfunction "1_1") (pintype "passive"))
      (node (ref "D8") (pin "A") (pinfunction "A_A") (pintype "bidirectional"))
      (node (ref "D9") (pin "A") (pinfunction "A_A") (pintype "bidirectional"))
      (node (ref "IC3") (pin "12-VIN") (pinfunction "12-VIN_12-VIN") (pintype "bidirectional"))
      (node (ref "IC3") (pin "13-VIN") (pinfunction "13-VIN_13-VIN") (pintype "bidirectional"))
      (node (ref "IC3") (pin "VIN") (pinfunction "12-VIN_VIN") (pintype "bidirectional"))
      (node (ref "R12") (pin "2") (pinfunction "2_2") (pintype "passive"))
      (node (ref "TP10") (pin "TP") (pinfunction "TP_TP") (pintype "input"))
    )
    (net (code "72") (name "/XTAL1") (class "Default")
      (node (ref "IC5") (pin "3") (pinfunction "PCINT8/CLKI/XTAL1-PA0_3") (pintype "bidirectional"))
      (node (ref "IC6") (pin "XTAL1") (pinfunction "XTAL1_XTAL1") (pintype "bidirectional"))
    )
    (net (code "73") (name "/XTAL2") (class "Default")
      (node (ref "IC5") (pin "2") (pinfunction "PCINT9/XTAL2-PA1_2") (pintype "bidirectional"))
      (node (ref "IC6") (pin "XTAL2") (pinfunction "XTAL2_XTAL2") (pintype "bidirectional"))
    )
    (net (code "74") (name "Net-(C18-PadPOS)") (class "Default")
      (node (ref "C18") (pin "POS") (pinfunction "POS_POS") (pintype "bidirectional"))
      (node (ref "C19") (pin "POS") (pinfunction "POS_POS") (pintype "bidirectional"))
      (node (ref "R19") (pin "1") (pinfunction "1_1") (pintype "passive"))
    )
    (net (code "75") (name "Net-(D1-PadC)") (class "Default")
      (node (ref "D1") (pin "C") (pinfunction "C_C") (pintype "passive"))
      (node (ref "D2") (pin "C") (pinfunction "C_C") (pintype "passive"))
    )
    (net (code "76") (name "Net-(IC3-Pad9-L2)") (class "Default")
      (node (ref "IC3") (pin "9-L2") (pinfunction "9-L2_9-L2") (pintype "bidirectional"))
      (node (ref "L1") (pin "P$2") (pinfunction "P$2_P$2") (pintype "bidirectional"))
    )
    (net (code "77") (name "Net-(IC3-Pad11-L1)") (class "Default")
      (node (ref "IC3") (pin "11-L1") (pinfunction "11-L1_11-L1") (pintype "bidirectional"))
      (node (ref "L1") (pin "P$1") (pinfunction "P$1_P$1") (pintype "bidirectional"))
    )
    (net (code "78") (name "Net-(IC4-REFC_1)") (class "Default")
      (node (ref "C4") (pin "1") (pinfunction "1_1") (pintype "passive"))
      (node (ref "IC4") (pin "1_REFC") (pinfunction "REFC_1_1_REFC") (pintype "bidirectional"))
    )
    (net (code "79") (name "Net-(IC13-Pad9-L2)") (class "Default")
      (node (ref "IC13") (pin "9-L2") (pinfunction "9-L2_9-L2") (pintype "bidirectional"))
      (node (ref "L2") (pin "P$2") (pinfunction "P$2_P$2") (pintype "bidirectional"))
    )
    (net (code "80") (name "Net-(IC13-Pad11-L1)") (class "Default")
      (node (ref "IC13") (pin "11-L1") (pinfunction "11-L1_11-L1") (pintype "bidirectional"))
      (node (ref "L2") (pin "P$1") (pinfunction "P$1_P$1") (pintype "bidirectional"))
    )
    (net (code "81") (name "unconnected-(IC1-CMP1-Pad1)") (class "Default")
      (node (ref "IC1") (pin "1") (pinfunction "CMP1_1") (pintype "passive"))
    )
    (net (code "82") (name "unconnected-(IC1-CMP2-Pad8)") (class "Default")
      (node (ref "IC1") (pin "8") (pinfunction "CMP2_8") (pintype "passive"))
    )
    (net (code "83") (name "unconnected-(IC9-NC-PadNC1)") (class "Default")
      (node (ref "IC9") (pin "NC1") (pinfunction "NC_NC1") (pintype "no_connect"))
    )
    (net (code "84") (name "unconnected-(IC9-NC-PadNC2)") (class "Default")
      (node (ref "IC9") (pin "NC2") (pinfunction "NC_NC2") (pintype "no_connect"))
    )
    (net (code "85") (name "unconnected-(IC9-PadCLKOUT)") (class "Default")
      (node (ref "IC9") (pin "CLKOUT") (pinfunction "CLKOUT_CLKOUT") (pintype "bidirectional"))
    )
    (net (code "86") (name "unconnected-(IC9-PadOSC2)") (class "Default")
      (node (ref "IC9") (pin "OSC2") (pinfunction "OSC2_OSC2") (pintype "bidirectional"))
    )
    (net (code "87") (name "unconnected-(IC9-~{RX0BF}-Pad!RX0BF!)") (class "Default")
      (node (ref "IC9") (pin "!RX0BF!") (pinfunction "~{RX0BF}_!RX0BF!") (pintype "bidirectional"))
    )
    (net (code "88") (name "unconnected-(IC9-~{RX1BF}-Pad!RX1BF!)") (class "Default")
      (node (ref "IC9") (pin "!RX1BF!") (pinfunction "~{RX1BF}_!RX1BF!") (pintype "bidirectional"))
    )
    (net (code "89") (name "unconnected-(IC9-~{TX0RTS}-Pad!TX0RTS!)") (class "Default")
      (node (ref "IC9") (pin "!TX0RTS!") (pinfunction "~{TX0RTS}_!TX0RTS!") (pintype "bidirectional"))
    )
    (net (code "90") (name "unconnected-(IC9-~{TX1RTS}-Pad!TX1RTS!)") (class "Default")
      (node (ref "IC9") (pin "!TX1RTS!") (pinfunction "~{TX1RTS}_!TX1RTS!") (pintype "bidirectional"))
    )
    (net (code "91") (name "unconnected-(IC9-~{TX2RTS}-Pad!TX2RTS!)") (class "Default")
      (node (ref "IC9") (pin "!TX2RTS!") (pinfunction "~{TX2RTS}_!TX2RTS!") (pintype "bidirectional"))
    )
    (net (code "92") (name "unconnected-(IC11-A_8-Pad8_A)") (class "Default")
      (node (ref "IC11") (pin "8_A") (pinfunction "A_8_8_A") (pintype "bidirectional"))
    )
    (net (code "93") (name "unconnected-(IC12-PadSPLIT)") (class "Default")
      (node (ref "IC12") (pin "SPLIT") (pinfunction "SPLIT_SPLIT") (pintype "bidirectional"))
    )
  )
)
